# daughterboard_2sheetbackup.net
KiCad netlist of a schematic drawn in EAGLE
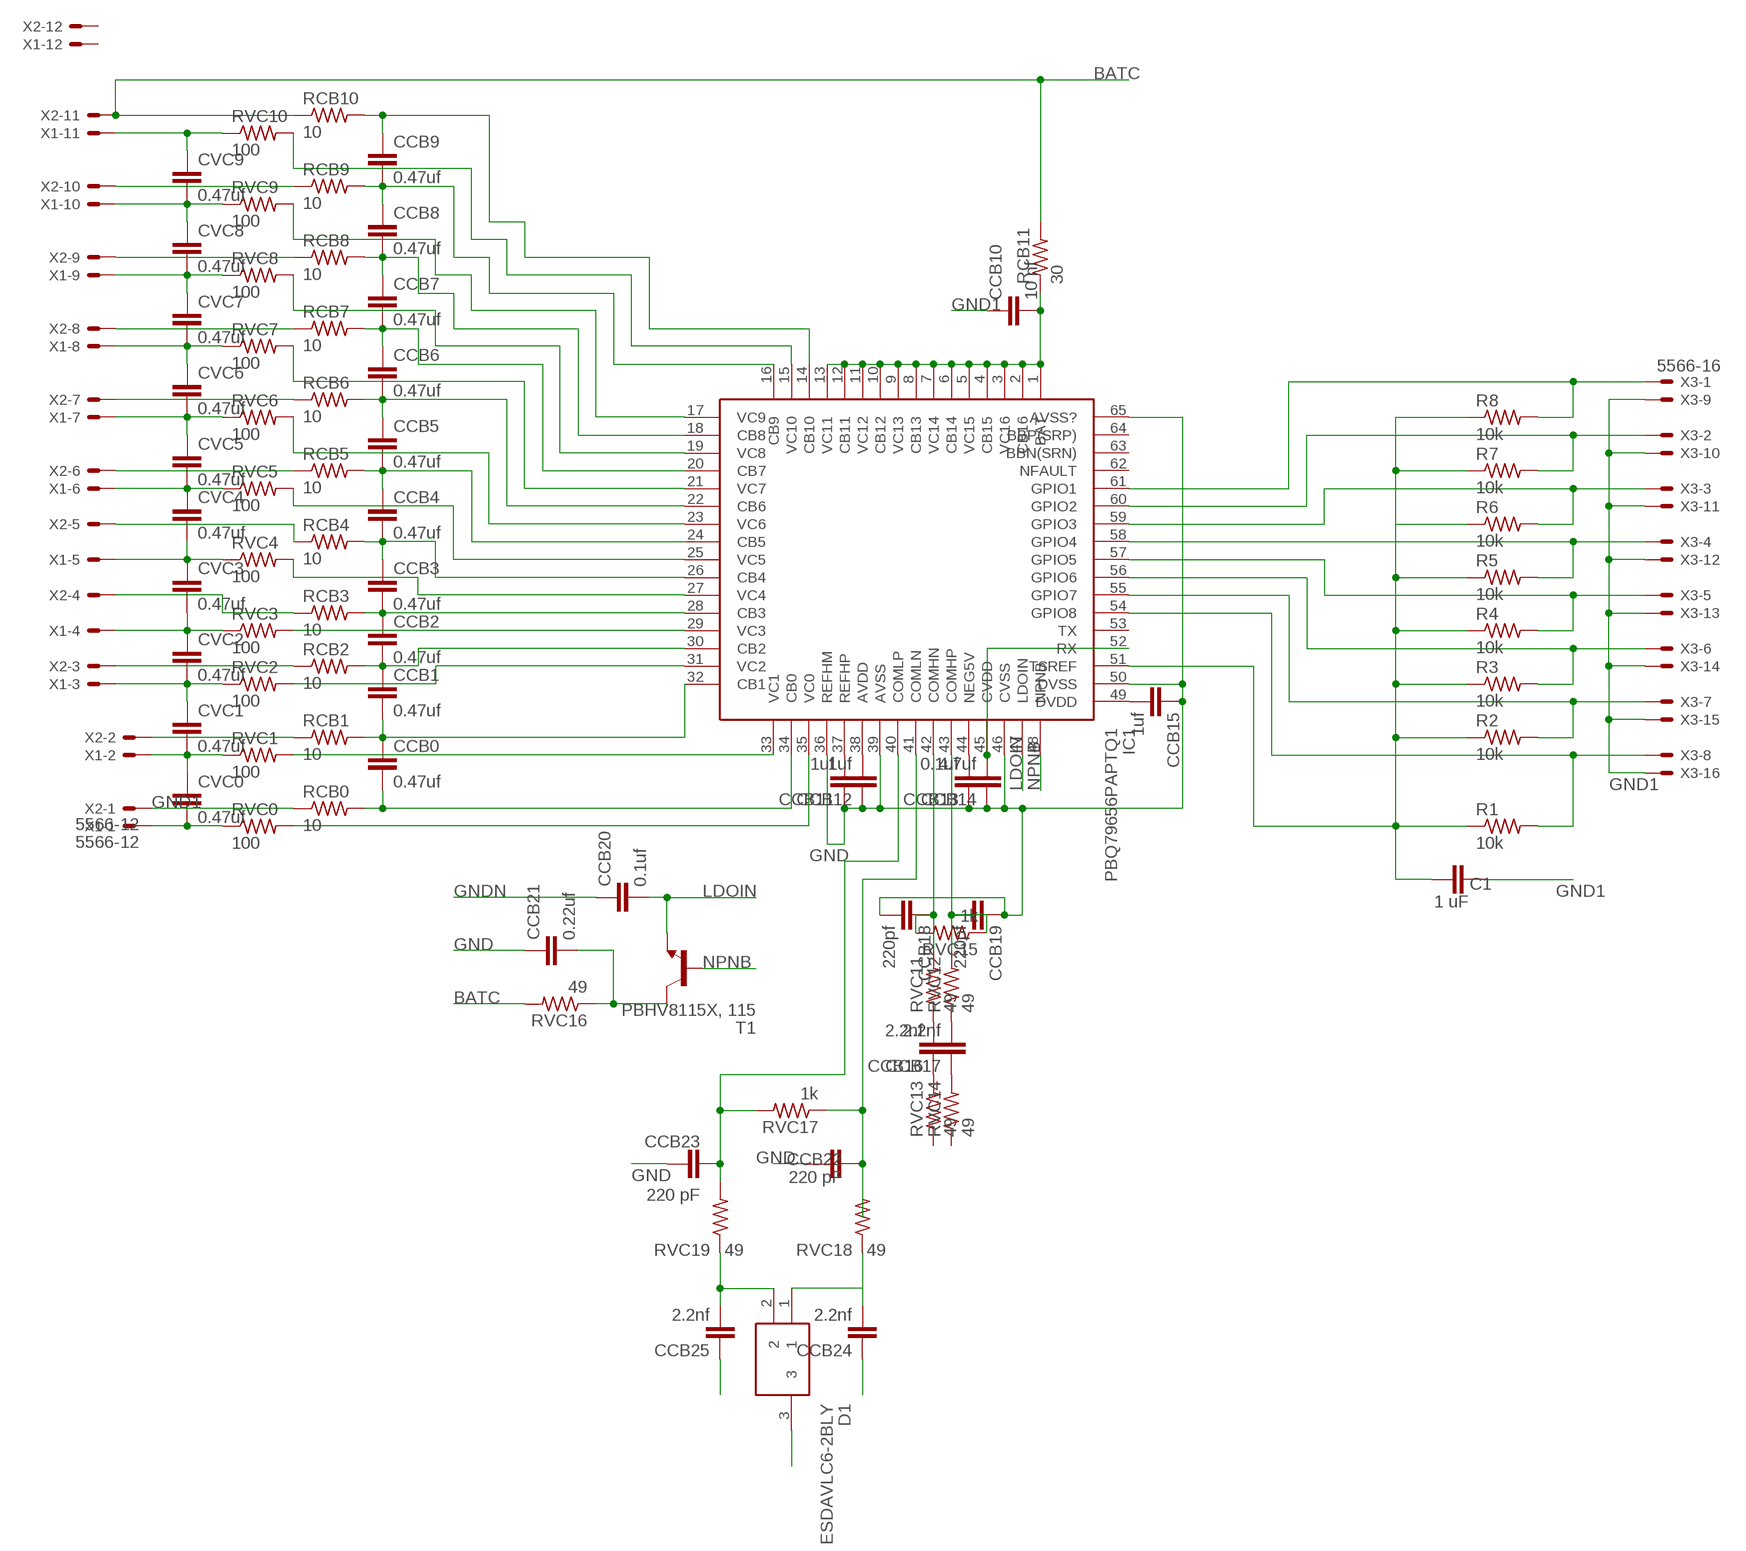
[diagram p0: schematic, sheet 1]
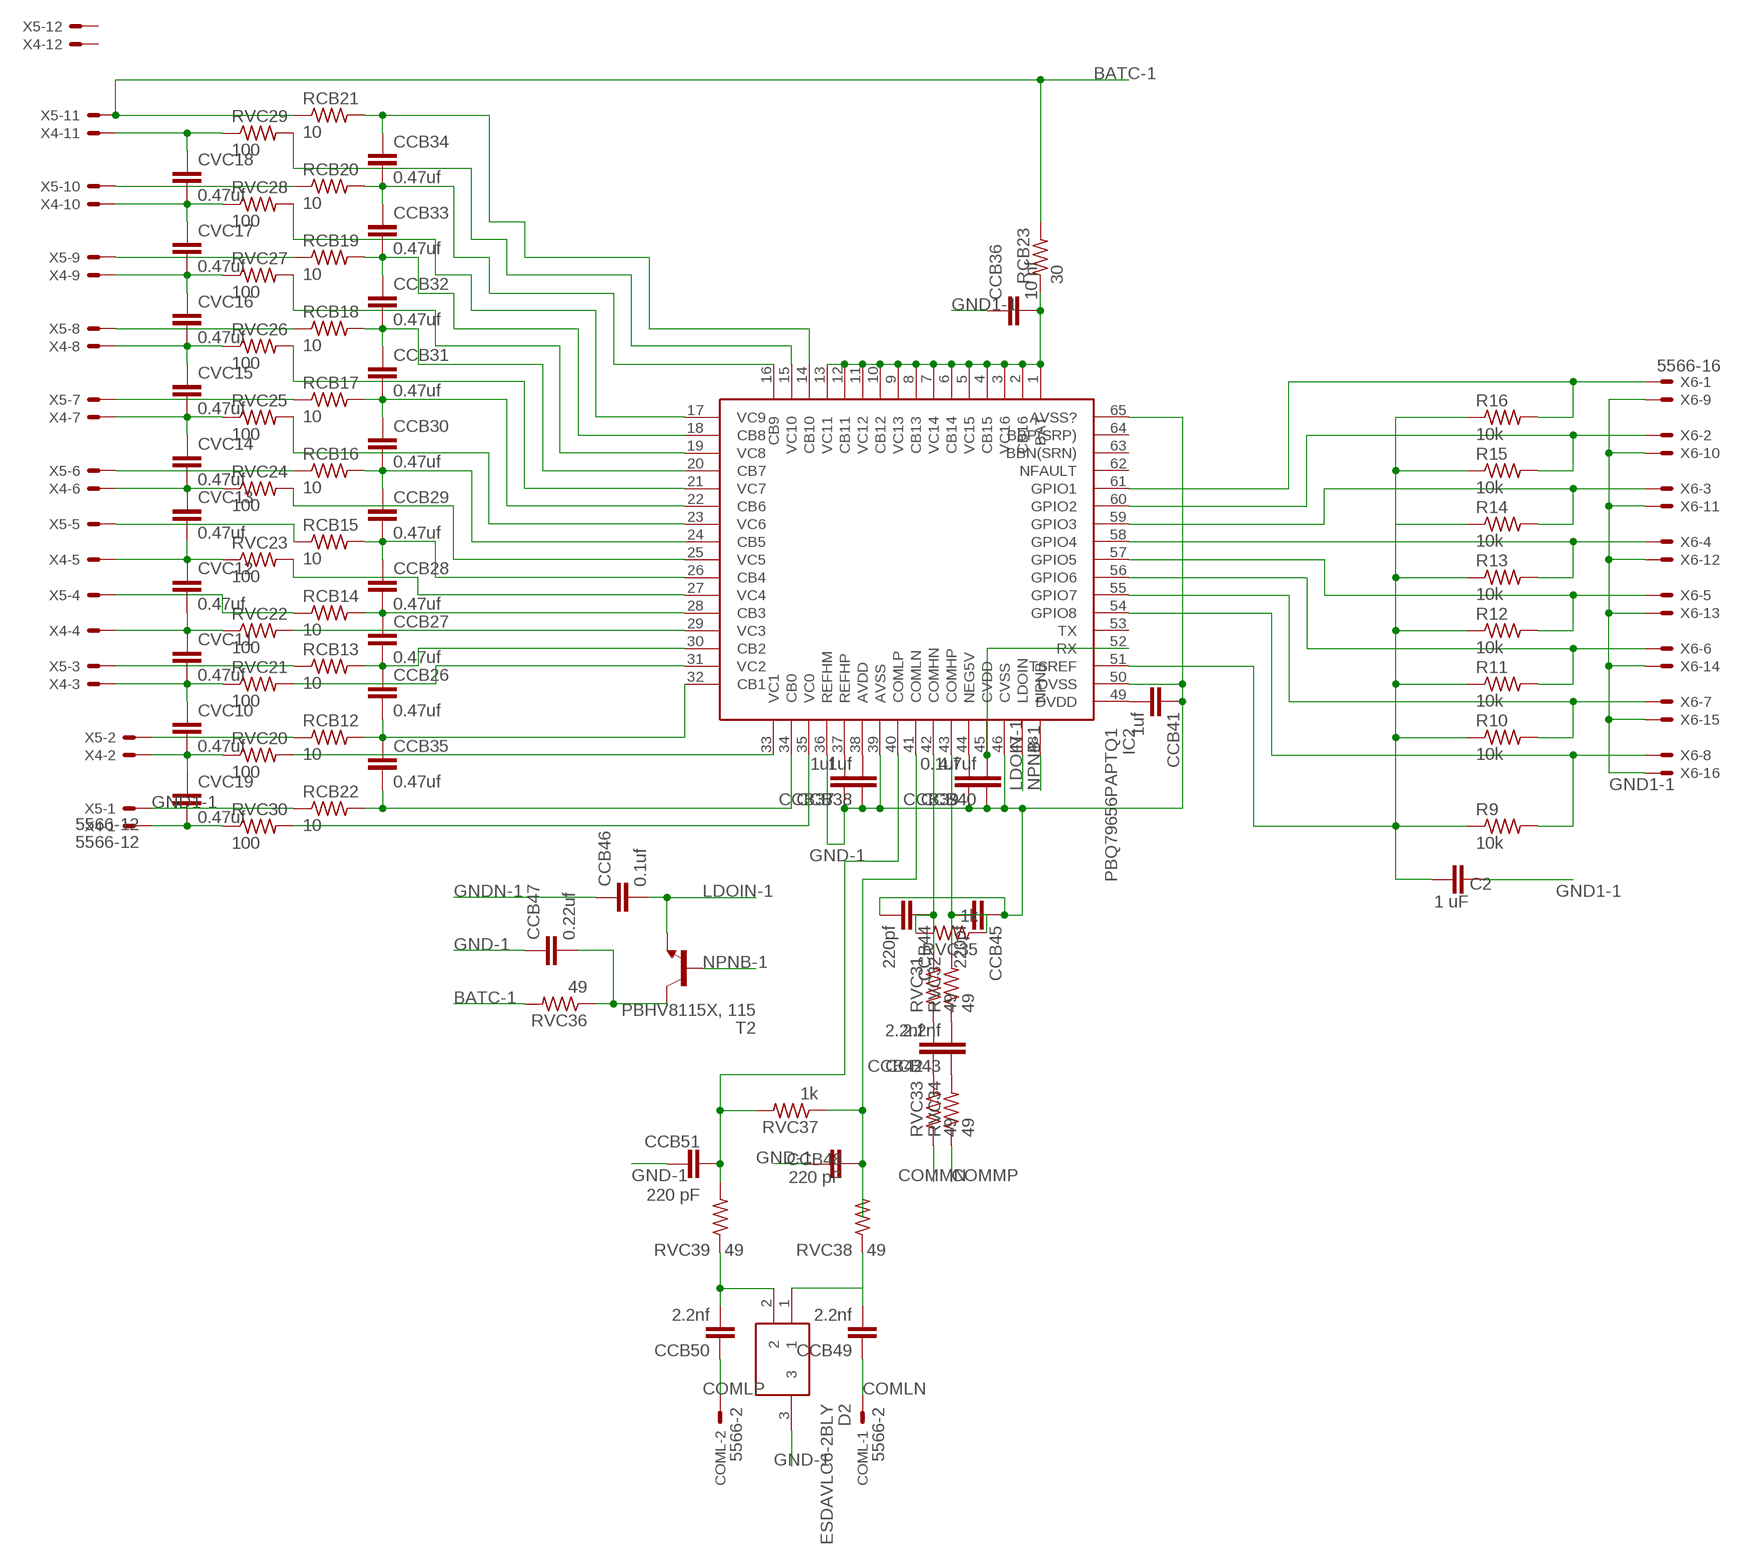
[diagram p1: schematic, sheet 2]

(export (version "E")
  (design (tool "Eeschema 10.0.6"))
  (components
    (comp (ref "C2")
      (value "1 uF")
      (footprint "eagle-import:C0603")
      (libsource (lib "eagle-import") (part "C-EUC0603"))
    )
    (comp (ref "CCB26")
      (value "0.47uf")
      (footprint "eagle-import:C0603")
      (libsource (lib "eagle-import") (part "C-EUC0603"))
    )
    (comp (ref "CCB27")
      (value "0.47uf")
      (footprint "eagle-import:C0603")
      (libsource (lib "eagle-import") (part "C-EUC0603"))
    )
    (comp (ref "CCB28")
      (value "0.47uf")
      (footprint "eagle-import:C0603")
      (libsource (lib "eagle-import") (part "C-EUC0603"))
    )
    (comp (ref "CCB29")
      (value "0.47uf")
      (footprint "eagle-import:C0603")
      (libsource (lib "eagle-import") (part "C-EUC0603"))
    )
    (comp (ref "CCB30")
      (value "0.47uf")
      (footprint "eagle-import:C0603")
      (libsource (lib "eagle-import") (part "C-EUC0603"))
    )
    (comp (ref "CCB31")
      (value "0.47uf")
      (footprint "eagle-import:C0603")
      (libsource (lib "eagle-import") (part "C-EUC0603"))
    )
    (comp (ref "CCB32")
      (value "0.47uf")
      (footprint "eagle-import:C0603")
      (libsource (lib "eagle-import") (part "C-EUC0603"))
    )
    (comp (ref "CCB33")
      (value "0.47uf")
      (footprint "eagle-import:C0603")
      (libsource (lib "eagle-import") (part "C-EUC0603"))
    )
    (comp (ref "CCB34")
      (value "0.47uf")
      (footprint "eagle-import:C0603")
      (libsource (lib "eagle-import") (part "C-EUC0603"))
    )
    (comp (ref "CCB35")
      (value "0.47uf")
      (footprint "eagle-import:C0603")
      (libsource (lib "eagle-import") (part "C-EUC0603"))
    )
    (comp (ref "CCB36")
      (value "10 nf")
      (footprint "eagle-import:C0603")
      (libsource (lib "eagle-import") (part "C-EUC0603"))
    )
    (comp (ref "CCB37")
      (value "1uf")
      (footprint "eagle-import:C0603")
      (libsource (lib "eagle-import") (part "C-EUC0603"))
    )
    (comp (ref "CCB38")
      (value "1uf")
      (footprint "eagle-import:C0603")
      (libsource (lib "eagle-import") (part "C-EUC0603"))
    )
    (comp (ref "CCB39")
      (value "0.1uf")
      (footprint "eagle-import:C0603")
      (libsource (lib "eagle-import") (part "C-EUC0603"))
    )
    (comp (ref "CCB40")
      (value "4.7uf")
      (footprint "eagle-import:C0603")
      (libsource (lib "eagle-import") (part "C-EUC0603"))
    )
    (comp (ref "CCB41")
      (value "1uf")
      (footprint "eagle-import:C0603")
      (libsource (lib "eagle-import") (part "C-EUC0603"))
    )
    (comp (ref "CCB42")
      (value "2.2nf")
      (footprint "eagle-import:C0603")
      (libsource (lib "eagle-import") (part "C-EUC0603"))
    )
    (comp (ref "CCB43")
      (value "2.2nf")
      (footprint "eagle-import:C0603")
      (libsource (lib "eagle-import") (part "C-EUC0603"))
    )
    (comp (ref "CCB44")
      (value "220pf")
      (footprint "eagle-import:C0603")
      (libsource (lib "eagle-import") (part "C-EUC0603"))
    )
    (comp (ref "CCB45")
      (value "220pf")
      (footprint "eagle-import:C0603")
      (libsource (lib "eagle-import") (part "C-EUC0603"))
    )
    (comp (ref "CCB46")
      (value "0.1uf")
      (footprint "eagle-import:C0603")
      (libsource (lib "eagle-import") (part "C-EUC0603"))
    )
    (comp (ref "CCB47")
      (value "0.22uf")
      (footprint "eagle-import:C0603")
      (libsource (lib "eagle-import") (part "C-EUC0603"))
    )
    (comp (ref "CCB48")
      (value "220 pF")
      (footprint "eagle-import:C0603")
      (libsource (lib "eagle-import") (part "C-EUC0603"))
    )
    (comp (ref "CCB49")
      (value "2.2nf")
      (footprint "eagle-import:C0603")
      (libsource (lib "eagle-import") (part "C-EUC0603"))
    )
    (comp (ref "CCB50")
      (value "2.2nf")
      (footprint "eagle-import:C0603")
      (libsource (lib "eagle-import") (part "C-EUC0603"))
    )
    (comp (ref "CCB51")
      (value "220 pF")
      (footprint "eagle-import:C0603")
      (libsource (lib "eagle-import") (part "C-EUC0603"))
    )
    (comp (ref "COML")
      (value "5566-2")
      (footprint "eagle-import:5566-2")
      (fields (field (name "MF") "MOLEX"))
      (libsource (lib "eagle-import") (part "5566-2"))
    )
    (comp (ref "CVC10")
      (value "0.47uf")
      (footprint "eagle-import:C0603")
      (libsource (lib "eagle-import") (part "C-EUC0603"))
    )
    (comp (ref "CVC11")
      (value "0.47uf")
      (footprint "eagle-import:C0603")
      (libsource (lib "eagle-import") (part "C-EUC0603"))
    )
    (comp (ref "CVC12")
      (value "0.47uf")
      (footprint "eagle-import:C0603")
      (libsource (lib "eagle-import") (part "C-EUC0603"))
    )
    (comp (ref "CVC13")
      (value "0.47uf")
      (footprint "eagle-import:C0603")
      (libsource (lib "eagle-import") (part "C-EUC0603"))
    )
    (comp (ref "CVC14")
      (value "0.47uf")
      (footprint "eagle-import:C0603")
      (libsource (lib "eagle-import") (part "C-EUC0603"))
    )
    (comp (ref "CVC15")
      (value "0.47uf")
      (footprint "eagle-import:C0603")
      (libsource (lib "eagle-import") (part "C-EUC0603"))
    )
    (comp (ref "CVC16")
      (value "0.47uf")
      (footprint "eagle-import:C0603")
      (libsource (lib "eagle-import") (part "C-EUC0603"))
    )
    (comp (ref "CVC17")
      (value "0.47uf")
      (footprint "eagle-import:C0603")
      (libsource (lib "eagle-import") (part "C-EUC0603"))
    )
    (comp (ref "CVC18")
      (value "0.47uf")
      (footprint "eagle-import:C0603")
      (libsource (lib "eagle-import") (part "C-EUC0603"))
    )
    (comp (ref "CVC19")
      (value "0.47uf")
      (footprint "eagle-import:C0603")
      (libsource (lib "eagle-import") (part "C-EUC0603"))
    )
    (comp (ref "D2")
      (value "ESDAVLC6-2BLY")
      (footprint "eagle-import:SOT95P255X150-3N")
      (fields (field (name "MOUSER_PART_NUMBER") "511-ESDAVLC6-2BLY"))
      (libsource (lib "eagle-import") (part "ESDAVLC6-2BLY"))
    )
    (comp (ref "IC2")
      (value "PBQ79656PAPTQ1")
      (footprint "eagle-import:QFP50P1200X1200X120-65N")
      (libsource (lib "eagle-import") (part "PBQ79656PAPTQ1"))
    )
    (comp (ref "R9")
      (value "10k")
      (footprint "eagle-import:R0603")
      (libsource (lib "eagle-import") (part "R-US_R0603"))
    )
    (comp (ref "R10")
      (value "10k")
      (footprint "eagle-import:R0603")
      (libsource (lib "eagle-import") (part "R-US_R0603"))
    )
    (comp (ref "R11")
      (value "10k")
      (footprint "eagle-import:R0603")
      (libsource (lib "eagle-import") (part "R-US_R0603"))
    )
    (comp (ref "R12")
      (value "10k")
      (footprint "eagle-import:R0603")
      (libsource (lib "eagle-import") (part "R-US_R0603"))
    )
    (comp (ref "R13")
      (value "10k")
      (footprint "eagle-import:R0603")
      (libsource (lib "eagle-import") (part "R-US_R0603"))
    )
    (comp (ref "R14")
      (value "10k")
      (footprint "eagle-import:R0603")
      (libsource (lib "eagle-import") (part "R-US_R0603"))
    )
    (comp (ref "R15")
      (value "10k")
      (footprint "eagle-import:R0603")
      (libsource (lib "eagle-import") (part "R-US_R0603"))
    )
    (comp (ref "R16")
      (value "10k")
      (footprint "eagle-import:R0603")
      (libsource (lib "eagle-import") (part "R-US_R0603"))
    )
    (comp (ref "RCB12")
      (value "10")
      (footprint "eagle-import:R0603")
      (libsource (lib "eagle-import") (part "R-US_R0603"))
    )
    (comp (ref "RCB13")
      (value "10")
      (footprint "eagle-import:R0603")
      (libsource (lib "eagle-import") (part "R-US_R0603"))
    )
    (comp (ref "RCB14")
      (value "10")
      (footprint "eagle-import:R0603")
      (libsource (lib "eagle-import") (part "R-US_R0603"))
    )
    (comp (ref "RCB15")
      (value "10")
      (footprint "eagle-import:R0603")
      (libsource (lib "eagle-import") (part "R-US_R0603"))
    )
    (comp (ref "RCB16")
      (value "10")
      (footprint "eagle-import:R0603")
      (libsource (lib "eagle-import") (part "R-US_R0603"))
    )
    (comp (ref "RCB17")
      (value "10")
      (footprint "eagle-import:R0603")
      (libsource (lib "eagle-import") (part "R-US_R0603"))
    )
    (comp (ref "RCB18")
      (value "10")
      (footprint "eagle-import:R0603")
      (libsource (lib "eagle-import") (part "R-US_R0603"))
    )
    (comp (ref "RCB19")
      (value "10")
      (footprint "eagle-import:R0603")
      (libsource (lib "eagle-import") (part "R-US_R0603"))
    )
    (comp (ref "RCB20")
      (value "10")
      (footprint "eagle-import:R0603")
      (libsource (lib "eagle-import") (part "R-US_R0603"))
    )
    (comp (ref "RCB21")
      (value "10")
      (footprint "eagle-import:R0603")
      (libsource (lib "eagle-import") (part "R-US_R0603"))
    )
    (comp (ref "RCB22")
      (value "10")
      (footprint "eagle-import:R0603")
      (libsource (lib "eagle-import") (part "R-US_R0603"))
    )
    (comp (ref "RCB23")
      (value "30")
      (footprint "eagle-import:R0603")
      (libsource (lib "eagle-import") (part "R-US_R0603"))
    )
    (comp (ref "RVC20")
      (value "100")
      (footprint "eagle-import:R0603")
      (libsource (lib "eagle-import") (part "R-US_R0603"))
    )
    (comp (ref "RVC21")
      (value "100")
      (footprint "eagle-import:R0603")
      (libsource (lib "eagle-import") (part "R-US_R0603"))
    )
    (comp (ref "RVC22")
      (value "100")
      (footprint "eagle-import:R0603")
      (libsource (lib "eagle-import") (part "R-US_R0603"))
    )
    (comp (ref "RVC23")
      (value "100")
      (footprint "eagle-import:R0603")
      (libsource (lib "eagle-import") (part "R-US_R0603"))
    )
    (comp (ref "RVC24")
      (value "100")
      (footprint "eagle-import:R0603")
      (libsource (lib "eagle-import") (part "R-US_R0603"))
    )
    (comp (ref "RVC25")
      (value "100")
      (footprint "eagle-import:R0603")
      (libsource (lib "eagle-import") (part "R-US_R0603"))
    )
    (comp (ref "RVC26")
      (value "100")
      (footprint "eagle-import:R0603")
      (libsource (lib "eagle-import") (part "R-US_R0603"))
    )
    (comp (ref "RVC27")
      (value "100")
      (footprint "eagle-import:R0603")
      (libsource (lib "eagle-import") (part "R-US_R0603"))
    )
    (comp (ref "RVC28")
      (value "100")
      (footprint "eagle-import:R0603")
      (libsource (lib "eagle-import") (part "R-US_R0603"))
    )
    (comp (ref "RVC29")
      (value "100")
      (footprint "eagle-import:R0603")
      (libsource (lib "eagle-import") (part "R-US_R0603"))
    )
    (comp (ref "RVC30")
      (value "100")
      (footprint "eagle-import:R0603")
      (libsource (lib "eagle-import") (part "R-US_R0603"))
    )
    (comp (ref "RVC31")
      (value "49")
      (footprint "eagle-import:R0603")
      (libsource (lib "eagle-import") (part "R-US_R0603"))
    )
    (comp (ref "RVC32")
      (value "49")
      (footprint "eagle-import:R0603")
      (libsource (lib "eagle-import") (part "R-US_R0603"))
    )
    (comp (ref "RVC33")
      (value "49")
      (footprint "eagle-import:R0603")
      (libsource (lib "eagle-import") (part "R-US_R0603"))
    )
    (comp (ref "RVC34")
      (value "49")
      (footprint "eagle-import:R0603")
      (libsource (lib "eagle-import") (part "R-US_R0603"))
    )
    (comp (ref "RVC35")
      (value "1k")
      (footprint "eagle-import:R0603")
      (libsource (lib "eagle-import") (part "R-US_R0603"))
    )
    (comp (ref "RVC36")
      (value "49")
      (footprint "eagle-import:R0603")
      (libsource (lib "eagle-import") (part "R-US_R0603"))
    )
    (comp (ref "RVC37")
      (value "1k")
      (footprint "eagle-import:R0603")
      (libsource (lib "eagle-import") (part "R-US_R0603"))
    )
    (comp (ref "RVC38")
      (value "49")
      (footprint "eagle-import:R0603")
      (libsource (lib "eagle-import") (part "R-US_R0603"))
    )
    (comp (ref "RVC39")
      (value "49")
      (footprint "eagle-import:R0603")
      (libsource (lib "eagle-import") (part "R-US_R0603"))
    )
    (comp (ref "T2")
      (value "PBHV8115X, 115")
      (footprint "eagle-import:SOT89-BCE")
      (libsource (lib "eagle-import") (part "-NPN-SOT89-BCEBC868"))
    )
    (comp (ref "X4")
      (value "5566-12")
      (footprint "eagle-import:5566-12")
      (fields (field (name "MF") "MOLEX"))
      (libsource (lib "eagle-import") (part "5566-12"))
    )
    (comp (ref "X5")
      (value "5566-12")
      (footprint "eagle-import:5566-12")
      (fields (field (name "MF") "MOLEX"))
      (libsource (lib "eagle-import") (part "5566-12"))
    )
    (comp (ref "X6")
      (value "5566-16")
      (footprint "eagle-import:5566-16")
      (fields (field (name "MF") "MOLEX"))
      (libsource (lib "eagle-import") (part "5566-16"))
    )
    (comp (ref "C1")
      (value "1 uF")
      (footprint "eagle-import:C2.5-2")
      (libsource (lib "eagle-import") (part "C2.5/2"))
    )
    (comp (ref "CCB0")
      (value "0.47uf")
      (footprint "eagle-import:C2.5-2")
      (libsource (lib "eagle-import") (part "C2.5/2"))
    )
    (comp (ref "CCB1")
      (value "0.47uf")
      (footprint "eagle-import:C2.5-2")
      (libsource (lib "eagle-import") (part "C2.5/2"))
    )
    (comp (ref "CCB2")
      (value "0.47uf")
      (footprint "eagle-import:C2.5-2")
      (libsource (lib "eagle-import") (part "C2.5/2"))
    )
    (comp (ref "CCB3")
      (value "0.47uf")
      (footprint "eagle-import:C2.5-2")
      (libsource (lib "eagle-import") (part "C2.5/2"))
    )
    (comp (ref "CCB4")
      (value "0.47uf")
      (footprint "eagle-import:C2.5-2")
      (libsource (lib "eagle-import") (part "C2.5/2"))
    )
    (comp (ref "CCB5")
      (value "0.47uf")
      (footprint "eagle-import:C2.5-2")
      (libsource (lib "eagle-import") (part "C2.5/2"))
    )
    (comp (ref "CCB6")
      (value "0.47uf")
      (footprint "eagle-import:C2.5-2")
      (libsource (lib "eagle-import") (part "C2.5/2"))
    )
    (comp (ref "CCB7")
      (value "0.47uf")
      (footprint "eagle-import:C2.5-2")
      (libsource (lib "eagle-import") (part "C2.5/2"))
    )
    (comp (ref "CCB8")
      (value "0.47uf")
      (footprint "eagle-import:C2.5-2")
      (libsource (lib "eagle-import") (part "C2.5/2"))
    )
    (comp (ref "CCB9")
      (value "0.47uf")
      (footprint "eagle-import:C2.5-2")
      (libsource (lib "eagle-import") (part "C2.5/2"))
    )
    (comp (ref "CCB10")
      (value "10 nf")
      (footprint "eagle-import:C2.5-2")
      (libsource (lib "eagle-import") (part "C2.5/2"))
    )
    (comp (ref "CCB11")
      (value "1uf")
      (footprint "eagle-import:C2.5-2")
      (libsource (lib "eagle-import") (part "C2.5/2"))
    )
    (comp (ref "CCB12")
      (value "1uf")
      (footprint "eagle-import:C2.5-2")
      (libsource (lib "eagle-import") (part "C2.5/2"))
    )
    (comp (ref "CCB13")
      (value "0.1uf")
      (footprint "eagle-import:C2.5-2")
      (libsource (lib "eagle-import") (part "C2.5/2"))
    )
    (comp (ref "CCB14")
      (value "4.7uf")
      (footprint "eagle-import:C2.5-2")
      (libsource (lib "eagle-import") (part "C2.5/2"))
    )
    (comp (ref "CCB15")
      (value "1uf")
      (footprint "eagle-import:C2.5-2")
      (libsource (lib "eagle-import") (part "C2.5/2"))
    )
    (comp (ref "CCB16")
      (value "2.2nf")
      (footprint "eagle-import:C2.5-2")
      (libsource (lib "eagle-import") (part "C2.5/2"))
    )
    (comp (ref "CCB17")
      (value "2.2nf")
      (footprint "eagle-import:C2.5-2")
      (libsource (lib "eagle-import") (part "C2.5/2"))
    )
    (comp (ref "CCB18")
      (value "220pf")
      (footprint "eagle-import:C2.5-2")
      (libsource (lib "eagle-import") (part "C2.5/2"))
    )
    (comp (ref "CCB19")
      (value "220pf")
      (footprint "eagle-import:C2.5-2")
      (libsource (lib "eagle-import") (part "C2.5/2"))
    )
    (comp (ref "CCB20")
      (value "0.1uf")
      (footprint "eagle-import:C2.5-2")
      (libsource (lib "eagle-import") (part "C2.5/2"))
    )
    (comp (ref "CCB21")
      (value "0.22uf")
      (footprint "eagle-import:C2.5-2")
      (libsource (lib "eagle-import") (part "C2.5/2"))
    )
    (comp (ref "CCB22")
      (value "220 pF")
      (footprint "eagle-import:C2.5-2")
      (libsource (lib "eagle-import") (part "C2.5/2"))
    )
    (comp (ref "CCB23")
      (value "220 pF")
      (footprint "eagle-import:C2.5-2")
      (libsource (lib "eagle-import") (part "C2.5/2"))
    )
    (comp (ref "CCB24")
      (value "2.2nf")
      (footprint "eagle-import:C2.5-2")
      (libsource (lib "eagle-import") (part "C2.5/2"))
    )
    (comp (ref "CCB25")
      (value "2.2nf")
      (footprint "eagle-import:C2.5-2")
      (libsource (lib "eagle-import") (part "C2.5/2"))
    )
    (comp (ref "CVC0")
      (value "0.47uf")
      (footprint "eagle-import:C2.5-2")
      (libsource (lib "eagle-import") (part "C2.5/2"))
    )
    (comp (ref "CVC1")
      (value "0.47uf")
      (footprint "eagle-import:C2.5-2")
      (libsource (lib "eagle-import") (part "C2.5/2"))
    )
    (comp (ref "CVC2")
      (value "0.47uf")
      (footprint "eagle-import:C2.5-2")
      (libsource (lib "eagle-import") (part "C2.5/2"))
    )
    (comp (ref "CVC3")
      (value "0.47uf")
      (footprint "eagle-import:C2.5-2")
      (libsource (lib "eagle-import") (part "C2.5/2"))
    )
    (comp (ref "CVC4")
      (value "0.47uf")
      (footprint "eagle-import:C2.5-2")
      (libsource (lib "eagle-import") (part "C2.5/2"))
    )
    (comp (ref "CVC5")
      (value "0.47uf")
      (footprint "eagle-import:C2.5-2")
      (libsource (lib "eagle-import") (part "C2.5/2"))
    )
    (comp (ref "CVC6")
      (value "0.47uf")
      (footprint "eagle-import:C2.5-2")
      (libsource (lib "eagle-import") (part "C2.5/2"))
    )
    (comp (ref "CVC7")
      (value "0.47uf")
      (footprint "eagle-import:C2.5-2")
      (libsource (lib "eagle-import") (part "C2.5/2"))
    )
    (comp (ref "CVC8")
      (value "0.47uf")
      (footprint "eagle-import:C2.5-2")
      (libsource (lib "eagle-import") (part "C2.5/2"))
    )
    (comp (ref "CVC9")
      (value "0.47uf")
      (footprint "eagle-import:C2.5-2")
      (libsource (lib "eagle-import") (part "C2.5/2"))
    )
    (comp (ref "D1")
      (value "ESDAVLC6-2BLY")
      (footprint "eagle-import:SOT95P255X150-3N")
      (fields (field (name "MOUSER_PART_NUMBER") "511-ESDAVLC6-2BLY"))
      (libsource (lib "eagle-import") (part "ESDAVLC6-2BLY"))
    )
    (comp (ref "IC1")
      (value "PBQ79656PAPTQ1")
      (footprint "eagle-import:QFP50P1200X1200X120-65N")
      (libsource (lib "eagle-import") (part "PBQ79656PAPTQ1"))
    )
    (comp (ref "R1")
      (value "10k")
      (footprint "eagle-import:R0603")
      (libsource (lib "eagle-import") (part "R-US_R0603"))
    )
    (comp (ref "R2")
      (value "10k")
      (footprint "eagle-import:R0603")
      (libsource (lib "eagle-import") (part "R-US_R0603"))
    )
    (comp (ref "R3")
      (value "10k")
      (footprint "eagle-import:R0603")
      (libsource (lib "eagle-import") (part "R-US_R0603"))
    )
    (comp (ref "R4")
      (value "10k")
      (footprint "eagle-import:R0603")
      (libsource (lib "eagle-import") (part "R-US_R0603"))
    )
    (comp (ref "R5")
      (value "10k")
      (footprint "eagle-import:R0603")
      (libsource (lib "eagle-import") (part "R-US_R0603"))
    )
    (comp (ref "R6")
      (value "10k")
      (footprint "eagle-import:R0603")
      (libsource (lib "eagle-import") (part "R-US_R0603"))
    )
    (comp (ref "R7")
      (value "10k")
      (footprint "eagle-import:R0603")
      (libsource (lib "eagle-import") (part "R-US_R0603"))
    )
    (comp (ref "R8")
      (value "10k")
      (footprint "eagle-import:R0603")
      (libsource (lib "eagle-import") (part "R-US_R0603"))
    )
    (comp (ref "RCB0")
      (value "10")
      (footprint "eagle-import:R0603")
      (libsource (lib "eagle-import") (part "R-US_R0603"))
    )
    (comp (ref "RCB1")
      (value "10")
      (footprint "eagle-import:R0603")
      (libsource (lib "eagle-import") (part "R-US_R0603"))
    )
    (comp (ref "RCB2")
      (value "10")
      (footprint "eagle-import:R0603")
      (libsource (lib "eagle-import") (part "R-US_R0603"))
    )
    (comp (ref "RCB3")
      (value "10")
      (footprint "eagle-import:R0603")
      (libsource (lib "eagle-import") (part "R-US_R0603"))
    )
    (comp (ref "RCB4")
      (value "10")
      (footprint "eagle-import:R0603")
      (libsource (lib "eagle-import") (part "R-US_R0603"))
    )
    (comp (ref "RCB5")
      (value "10")
      (footprint "eagle-import:R0603")
      (libsource (lib "eagle-import") (part "R-US_R0603"))
    )
    (comp (ref "RCB6")
      (value "10")
      (footprint "eagle-import:R0603")
      (libsource (lib "eagle-import") (part "R-US_R0603"))
    )
    (comp (ref "RCB7")
      (value "10")
      (footprint "eagle-import:R0603")
      (libsource (lib "eagle-import") (part "R-US_R0603"))
    )
    (comp (ref "RCB8")
      (value "10")
      (footprint "eagle-import:R0603")
      (libsource (lib "eagle-import") (part "R-US_R0603"))
    )
    (comp (ref "RCB9")
      (value "10")
      (footprint "eagle-import:R0603")
      (libsource (lib "eagle-import") (part "R-US_R0603"))
    )
    (comp (ref "RCB10")
      (value "10")
      (footprint "eagle-import:R0603")
      (libsource (lib "eagle-import") (part "R-US_R0603"))
    )
    (comp (ref "RCB11")
      (value "30")
      (footprint "eagle-import:R0603")
      (libsource (lib "eagle-import") (part "R-US_R0603"))
    )
    (comp (ref "RVC0")
      (value "100")
      (footprint "eagle-import:R0603")
      (libsource (lib "eagle-import") (part "R-US_R0603"))
    )
    (comp (ref "RVC1")
      (value "100")
      (footprint "eagle-import:R0603")
      (libsource (lib "eagle-import") (part "R-US_R0603"))
    )
    (comp (ref "RVC2")
      (value "100")
      (footprint "eagle-import:R0603")
      (libsource (lib "eagle-import") (part "R-US_R0603"))
    )
    (comp (ref "RVC3")
      (value "100")
      (footprint "eagle-import:R0603")
      (libsource (lib "eagle-import") (part "R-US_R0603"))
    )
    (comp (ref "RVC4")
      (value "100")
      (footprint "eagle-import:R0603")
      (libsource (lib "eagle-import") (part "R-US_R0603"))
    )
    (comp (ref "RVC5")
      (value "100")
      (footprint "eagle-import:R0603")
      (libsource (lib "eagle-import") (part "R-US_R0603"))
    )
    (comp (ref "RVC6")
      (value "100")
      (footprint "eagle-import:R0603")
      (libsource (lib "eagle-import") (part "R-US_R0603"))
    )
    (comp (ref "RVC7")
      (value "100")
      (footprint "eagle-import:R0603")
      (libsource (lib "eagle-import") (part "R-US_R0603"))
    )
    (comp (ref "RVC8")
      (value "100")
      (footprint "eagle-import:R0603")
      (libsource (lib "eagle-import") (part "R-US_R0603"))
    )
    (comp (ref "RVC9")
      (value "100")
      (footprint "eagle-import:R0603")
      (libsource (lib "eagle-import") (part "R-US_R0603"))
    )
    (comp (ref "RVC10")
      (value "100")
      (footprint "eagle-import:R0603")
      (libsource (lib "eagle-import") (part "R-US_R0603"))
    )
    (comp (ref "RVC11")
      (value "49")
      (footprint "eagle-import:R0603")
      (libsource (lib "eagle-import") (part "R-US_R0603"))
    )
    (comp (ref "RVC12")
      (value "49")
      (footprint "eagle-import:R0603")
      (libsource (lib "eagle-import") (part "R-US_R0603"))
    )
    (comp (ref "RVC13")
      (value "49")
      (footprint "eagle-import:R0603")
      (libsource (lib "eagle-import") (part "R-US_R0603"))
    )
    (comp (ref "RVC14")
      (value "49")
      (footprint "eagle-import:R0603")
      (libsource (lib "eagle-import") (part "R-US_R0603"))
    )
    (comp (ref "RVC15")
      (value "1k")
      (footprint "eagle-import:R0603")
      (libsource (lib "eagle-import") (part "R-US_R0603"))
    )
    (comp (ref "RVC16")
      (value "49")
      (footprint "eagle-import:R0603")
      (libsource (lib "eagle-import") (part "R-US_R0603"))
    )
    (comp (ref "RVC17")
      (value "1k")
      (footprint "eagle-import:R0603")
      (libsource (lib "eagle-import") (part "R-US_R0603"))
    )
    (comp (ref "RVC18")
      (value "49")
      (footprint "eagle-import:R0603")
      (libsource (lib "eagle-import") (part "R-US_R0603"))
    )
    (comp (ref "RVC19")
      (value "49")
      (footprint "eagle-import:R0603")
      (libsource (lib "eagle-import") (part "R-US_R0603"))
    )
    (comp (ref "T1")
      (value "PBHV8115X, 115")
      (footprint "eagle-import:SOT89-BCE")
      (libsource (lib "eagle-import") (part "-NPN-SOT89-BCEBC868"))
    )
    (comp (ref "X1")
      (value "5566-12")
      (footprint "eagle-import:5566-12")
      (fields (field (name "MF") "MOLEX"))
      (libsource (lib "eagle-import") (part "5566-12"))
    )
    (comp (ref "X2")
      (value "5566-12")
      (footprint "eagle-import:5566-12")
      (fields (field (name "MF") "MOLEX"))
      (libsource (lib "eagle-import") (part "5566-12"))
    )
    (comp (ref "X3")
      (value "5566-16")
      (footprint "eagle-import:5566-16")
      (fields (field (name "MF") "MOLEX"))
      (libsource (lib "eagle-import") (part "5566-16"))
    )
  )
  (nets
    (net (code "1") (name "BATC") (class "Default")
      (node (ref "RCB10") (pin "1") (pinfunction "1_1") (pintype "passive"))
      (node (ref "RCB11") (pin "2") (pinfunction "2_2") (pintype "passive"))
      (node (ref "RVC16") (pin "2") (pinfunction "2_2") (pintype "passive"))
      (node (ref "X2") (pin "11") (pinfunction "S_11") (pintype "passive"))
    )
    (net (code "2") (name "BATC-1") (class "Default")
      (node (ref "RCB21") (pin "1") (pinfunction "1_1") (pintype "passive"))
      (node (ref "RCB23") (pin "2") (pinfunction "2_2") (pintype "passive"))
      (node (ref "RVC36") (pin "2") (pinfunction "2_2") (pintype "passive"))
      (node (ref "X5") (pin "11") (pinfunction "S_11") (pintype "passive"))
    )
    (net (code "3") (name "COMLN") (class "Default")
      (node (ref "CCB49") (pin "1") (pinfunction "1_1") (pintype "passive"))
      (node (ref "COML") (pin "1") (pinfunction "S_1") (pintype "passive"))
    )
    (net (code "4") (name "COMLP") (class "Default")
      (node (ref "CCB50") (pin "1") (pinfunction "1_1") (pintype "passive"))
      (node (ref "COML") (pin "2") (pinfunction "S_2") (pintype "passive"))
    )
    (net (code "5") (name "COMMN") (class "Default")
      (node (ref "RVC33") (pin "1") (pinfunction "1_1") (pintype "passive"))
    )
    (net (code "6") (name "COMMP") (class "Default")
      (node (ref "RVC34") (pin "1") (pinfunction "1_1") (pintype "passive"))
    )
    (net (code "7") (name "GND") (class "Default")
      (node (ref "CCB11") (pin "1") (pinfunction "1_1") (pintype "passive"))
      (node (ref "CCB12") (pin "1") (pinfunction "1_1") (pintype "passive"))
      (node (ref "CCB13") (pin "1") (pinfunction "1_1") (pintype "passive"))
      (node (ref "CCB14") (pin "1") (pinfunction "1_1") (pintype "passive"))
      (node (ref "CCB15") (pin "1") (pinfunction "1_1") (pintype "passive"))
      (node (ref "CCB18") (pin "2") (pinfunction "2_2") (pintype "passive"))
      (node (ref "CCB19") (pin "1") (pinfunction "1_1") (pintype "passive"))
      (node (ref "CCB21") (pin "1") (pinfunction "1_1") (pintype "passive"))
      (node (ref "CCB22") (pin "1") (pinfunction "1_1") (pintype "passive"))
      (node (ref "CCB23") (pin "1") (pinfunction "1_1") (pintype "passive"))
      (node (ref "D1") (pin "3") (pinfunction "3_3") (pintype "bidirectional"))
      (node (ref "IC1") (pin "36") (pinfunction "REFHM_36") (pintype "bidirectional"))
      (node (ref "IC1") (pin "39") (pinfunction "AVSS_39") (pintype "bidirectional"))
      (node (ref "IC1") (pin "46") (pinfunction "CVSS_46") (pintype "bidirectional"))
      (node (ref "IC1") (pin "50") (pinfunction "DVSS_50") (pintype "bidirectional"))
      (node (ref "IC1") (pin "65") (pinfunction "AVSS?_65") (pintype "bidirectional"))
    )
    (net (code "8") (name "GND-1") (class "Default")
      (node (ref "CCB37") (pin "1") (pinfunction "1_1") (pintype "passive"))
      (node (ref "CCB38") (pin "1") (pinfunction "1_1") (pintype "passive"))
      (node (ref "CCB39") (pin "1") (pinfunction "1_1") (pintype "passive"))
      (node (ref "CCB40") (pin "1") (pinfunction "1_1") (pintype "passive"))
      (node (ref "CCB41") (pin "1") (pinfunction "1_1") (pintype "passive"))
      (node (ref "CCB44") (pin "2") (pinfunction "2_2") (pintype "passive"))
      (node (ref "CCB45") (pin "1") (pinfunction "1_1") (pintype "passive"))
      (node (ref "CCB47") (pin "1") (pinfunction "1_1") (pintype "passive"))
      (node (ref "CCB48") (pin "1") (pinfunction "1_1") (pintype "passive"))
      (node (ref "CCB51") (pin "1") (pinfunction "1_1") (pintype "passive"))
      (node (ref "D2") (pin "3") (pinfunction "3_3") (pintype "bidirectional"))
      (node (ref "IC2") (pin "36") (pinfunction "REFHM_36") (pintype "bidirectional"))
      (node (ref "IC2") (pin "39") (pinfunction "AVSS_39") (pintype "bidirectional"))
      (node (ref "IC2") (pin "46") (pinfunction "CVSS_46") (pintype "bidirectional"))
      (node (ref "IC2") (pin "50") (pinfunction "DVSS_50") (pintype "bidirectional"))
      (node (ref "IC2") (pin "65") (pinfunction "AVSS?_65") (pintype "bidirectional"))
    )
    (net (code "9") (name "GND1") (class "Default")
      (node (ref "C1") (pin "1") (pinfunction "1_1") (pintype "passive"))
      (node (ref "CCB10") (pin "1") (pinfunction "1_1") (pintype "passive"))
      (node (ref "RCB0") (pin "1") (pinfunction "1_1") (pintype "passive"))
      (node (ref "X2") (pin "1") (pinfunction "S_1") (pintype "passive"))
      (node (ref "X3") (pin "10") (pinfunction "S_10") (pintype "passive"))
      (node (ref "X3") (pin "11") (pinfunction "S_11") (pintype "passive"))
      (node (ref "X3") (pin "12") (pinfunction "S_12") (pintype "passive"))
      (node (ref "X3") (pin "13") (pinfunction "S_13") (pintype "passive"))
      (node (ref "X3") (pin "14") (pinfunction "S_14") (pintype "passive"))
      (node (ref "X3") (pin "15") (pinfunction "S_15") (pintype "passive"))
      (node (ref "X3") (pin "16") (pinfunction "S_16") (pintype "passive"))
      (node (ref "X3") (pin "9") (pinfunction "S_9") (pintype "passive"))
    )
    (net (code "10") (name "GND1-1") (class "Default")
      (node (ref "C2") (pin "1") (pinfunction "1_1") (pintype "passive"))
      (node (ref "CCB36") (pin "1") (pinfunction "1_1") (pintype "passive"))
      (node (ref "RCB22") (pin "1") (pinfunction "1_1") (pintype "passive"))
      (node (ref "X5") (pin "1") (pinfunction "S_1") (pintype "passive"))
      (node (ref "X6") (pin "10") (pinfunction "S_10") (pintype "passive"))
      (node (ref "X6") (pin "11") (pinfunction "S_11") (pintype "passive"))
      (node (ref "X6") (pin "12") (pinfunction "S_12") (pintype "passive"))
      (node (ref "X6") (pin "13") (pinfunction "S_13") (pintype "passive"))
      (node (ref "X6") (pin "14") (pinfunction "S_14") (pintype "passive"))
      (node (ref "X6") (pin "15") (pinfunction "S_15") (pintype "passive"))
      (node (ref "X6") (pin "16") (pinfunction "S_16") (pintype "passive"))
      (node (ref "X6") (pin "9") (pinfunction "S_9") (pintype "passive"))
    )
    (net (code "11") (name "GNDN") (class "Default")
      (node (ref "CCB20") (pin "1") (pinfunction "1_1") (pintype "passive"))
    )
    (net (code "12") (name "GNDN-1") (class "Default")
      (node (ref "CCB46") (pin "1") (pinfunction "1_1") (pintype "passive"))
    )
    (net (code "13") (name "LDOIN") (class "Default")
      (node (ref "CCB20") (pin "2") (pinfunction "2_2") (pintype "passive"))
      (node (ref "IC1") (pin "47") (pinfunction "LDOIN_47") (pintype "bidirectional"))
      (node (ref "T1") (pin "E") (pinfunction "E_E") (pintype "passive"))
    )
    (net (code "14") (name "LDOIN-1") (class "Default")
      (node (ref "CCB46") (pin "2") (pinfunction "2_2") (pintype "passive"))
      (node (ref "IC2") (pin "47") (pinfunction "LDOIN_47") (pintype "bidirectional"))
      (node (ref "T2") (pin "E") (pinfunction "E_E") (pintype "passive"))
    )
    (net (code "15") (name "NPNB") (class "Default")
      (node (ref "IC1") (pin "48") (pinfunction "NPNB_48") (pintype "bidirectional"))
      (node (ref "T1") (pin "B") (pinfunction "B_B") (pintype "passive"))
    )
    (net (code "16") (name "NPNB-1") (class "Default")
      (node (ref "IC2") (pin "48") (pinfunction "NPNB_48") (pintype "bidirectional"))
      (node (ref "T2") (pin "B") (pinfunction "B_B") (pintype "passive"))
    )
    (net (code "17") (name "Net-(CCB16-Pad1)") (class "Default")
      (node (ref "CCB16") (pin "1") (pinfunction "1_1") (pintype "passive"))
      (node (ref "RVC13") (pin "2") (pinfunction "2_2") (pintype "passive"))
    )
    (net (code "18") (name "Net-(CCB16-Pad2)") (class "Default")
      (node (ref "CCB16") (pin "2") (pinfunction "2_2") (pintype "passive"))
      (node (ref "RVC11") (pin "1") (pinfunction "1_1") (pintype "passive"))
    )
    (net (code "19") (name "Net-(CCB17-Pad1)") (class "Default")
      (node (ref "CCB17") (pin "1") (pinfunction "1_1") (pintype "passive"))
      (node (ref "RVC14") (pin "2") (pinfunction "2_2") (pintype "passive"))
    )
    (net (code "20") (name "Net-(CCB17-Pad2)") (class "Default")
      (node (ref "CCB17") (pin "2") (pinfunction "2_2") (pintype "passive"))
      (node (ref "RVC12") (pin "1") (pinfunction "1_1") (pintype "passive"))
    )
    (net (code "21") (name "Net-(CCB21-Pad2)") (class "Default")
      (node (ref "CCB21") (pin "2") (pinfunction "2_2") (pintype "passive"))
      (node (ref "RVC16") (pin "1") (pinfunction "1_1") (pintype "passive"))
      (node (ref "T1") (pin "C") (pinfunction "C_C") (pintype "passive"))
    )
    (net (code "22") (name "Net-(CCB24-Pad2)") (class "Default")
      (node (ref "CCB24") (pin "2") (pinfunction "2_2") (pintype "passive"))
      (node (ref "D1") (pin "1") (pinfunction "1_1") (pintype "bidirectional"))
      (node (ref "RVC18") (pin "1") (pinfunction "1_1") (pintype "passive"))
    )
    (net (code "23") (name "Net-(CCB25-Pad2)") (class "Default")
      (node (ref "CCB25") (pin "2") (pinfunction "2_2") (pintype "passive"))
      (node (ref "D1") (pin "2") (pinfunction "2_2") (pintype "bidirectional"))
      (node (ref "RVC19") (pin "1") (pinfunction "1_1") (pintype "passive"))
    )
    (net (code "24") (name "Net-(CCB42-Pad1)") (class "Default")
      (node (ref "CCB42") (pin "1") (pinfunction "1_1") (pintype "passive"))
      (node (ref "RVC33") (pin "2") (pinfunction "2_2") (pintype "passive"))
    )
    (net (code "25") (name "Net-(CCB42-Pad2)") (class "Default")
      (node (ref "CCB42") (pin "2") (pinfunction "2_2") (pintype "passive"))
      (node (ref "RVC31") (pin "1") (pinfunction "1_1") (pintype "passive"))
    )
    (net (code "26") (name "Net-(CCB43-Pad1)") (class "Default")
      (node (ref "CCB43") (pin "1") (pinfunction "1_1") (pintype "passive"))
      (node (ref "RVC34") (pin "2") (pinfunction "2_2") (pintype "passive"))
    )
    (net (code "27") (name "Net-(CCB43-Pad2)") (class "Default")
      (node (ref "CCB43") (pin "2") (pinfunction "2_2") (pintype "passive"))
      (node (ref "RVC32") (pin "1") (pinfunction "1_1") (pintype "passive"))
    )
    (net (code "28") (name "Net-(CCB47-Pad2)") (class "Default")
      (node (ref "CCB47") (pin "2") (pinfunction "2_2") (pintype "passive"))
      (node (ref "RVC36") (pin "1") (pinfunction "1_1") (pintype "passive"))
      (node (ref "T2") (pin "C") (pinfunction "C_C") (pintype "passive"))
    )
    (net (code "29") (name "Net-(CCB49-Pad2)") (class "Default")
      (node (ref "CCB49") (pin "2") (pinfunction "2_2") (pintype "passive"))
      (node (ref "D2") (pin "1") (pinfunction "1_1") (pintype "bidirectional"))
      (node (ref "RVC38") (pin "1") (pinfunction "1_1") (pintype "passive"))
    )
    (net (code "30") (name "Net-(CCB50-Pad2)") (class "Default")
      (node (ref "CCB50") (pin "2") (pinfunction "2_2") (pintype "passive"))
      (node (ref "D2") (pin "2") (pinfunction "2_2") (pintype "bidirectional"))
      (node (ref "RVC39") (pin "1") (pinfunction "1_1") (pintype "passive"))
    )
    (net (code "31") (name "Net-(IC1-AVDD)") (class "Default")
      (node (ref "CCB12") (pin "2") (pinfunction "2_2") (pintype "passive"))
      (node (ref "IC1") (pin "38") (pinfunction "AVDD_38") (pintype "bidirectional"))
    )
    (net (code "32") (name "Net-(IC1-BAT)") (class "Default")
      (node (ref "CCB10") (pin "2") (pinfunction "2_2") (pintype "passive"))
      (node (ref "IC1") (pin "1") (pinfunction "BAT_1") (pintype "bidirectional"))
      (node (ref "IC1") (pin "10") (pinfunction "CB12_10") (pintype "bidirectional"))
      (node (ref "IC1") (pin "11") (pinfunction "VC12_11") (pintype "bidirectional"))
      (node (ref "IC1") (pin "12") (pinfunction "CB11_12") (pintype "bidirectional"))
      (node (ref "IC1") (pin "13") (pinfunction "VC11_13") (pintype "bidirectional"))
      (node (ref "IC1") (pin "2") (pinfunction "CB16_2") (pintype "bidirectional"))
      (node (ref "IC1") (pin "3") (pinfunction "VC16_3") (pintype "bidirectional"))
      (node (ref "IC1") (pin "4") (pinfunction "CB15_4") (pintype "bidirectional"))
      (node (ref "IC1") (pin "5") (pinfunction "VC15_5") (pintype "bidirectional"))
      (node (ref "IC1") (pin "6") (pinfunction "CB14_6") (pintype "bidirectional"))
      (node (ref "IC1") (pin "7") (pinfunction "VC14_7") (pintype "bidirectional"))
      (node (ref "IC1") (pin "8") (pinfunction "CB13_8") (pintype "bidirectional"))
      (node (ref "IC1") (pin "9") (pinfunction "VC13_9") (pintype "bidirectional"))
      (node (ref "RCB11") (pin "1") (pinfunction "1_1") (pintype "passive"))
    )
    (net (code "33") (name "Net-(IC1-CB0)") (class "Default")
      (node (ref "CCB0") (pin "2") (pinfunction "2_2") (pintype "passive"))
      (node (ref "IC1") (pin "34") (pinfunction "CB0_34") (pintype "bidirectional"))
      (node (ref "RCB0") (pin "2") (pinfunction "2_2") (pintype "passive"))
    )
    (net (code "34") (name "Net-(IC1-CB1)") (class "Default")
      (node (ref "CCB0") (pin "1") (pinfunction "1_1") (pintype "passive"))
      (node (ref "CCB1") (pin "2") (pinfunction "2_2") (pintype "passive"))
      (node (ref "IC1") (pin "32") (pinfunction "CB1_32") (pintype "bidirectional"))
      (node (ref "RCB1") (pin "2") (pinfunction "2_2") (pintype "passive"))
    )
    (net (code "35") (name "Net-(IC1-CB2)") (class "Default")
      (node (ref "CCB1") (pin "1") (pinfunction "1_1") (pintype "passive"))
      (node (ref "CCB2") (pin "2") (pinfunction "2_2") (pintype "passive"))
      (node (ref "IC1") (pin "30") (pinfunction "CB2_30") (pintype "bidirectional"))
      (node (ref "RCB2") (pin "2") (pinfunction "2_2") (pintype "passive"))
    )
    (net (code "36") (name "Net-(IC1-CB3)") (class "Default")
      (node (ref "CCB2") (pin "1") (pinfunction "1_1") (pintype "passive"))
      (node (ref "CCB3") (pin "2") (pinfunction "2_2") (pintype "passive"))
      (node (ref "IC1") (pin "28") (pinfunction "CB3_28") (pintype "bidirectional"))
      (node (ref "RCB3") (pin "2") (pinfunction "2_2") (pintype "passive"))
    )
    (net (code "37") (name "Net-(IC1-CB4)") (class "Default")
      (node (ref "CCB3") (pin "1") (pinfunction "1_1") (pintype "passive"))
      (node (ref "CCB4") (pin "2") (pinfunction "2_2") (pintype "passive"))
      (node (ref "IC1") (pin "26") (pinfunction "CB4_26") (pintype "bidirectional"))
      (node (ref "RCB4") (pin "2") (pinfunction "2_2") (pintype "passive"))
    )
    (net (code "38") (name "Net-(IC1-CB5)") (class "Default")
      (node (ref "CCB4") (pin "1") (pinfunction "1_1") (pintype "passive"))
      (node (ref "CCB5") (pin "2") (pinfunction "2_2") (pintype "passive"))
      (node (ref "IC1") (pin "24") (pinfunction "CB5_24") (pintype "bidirectional"))
      (node (ref "RCB5") (pin "2") (pinfunction "2_2") (pintype "passive"))
    )
    (net (code "39") (name "Net-(IC1-CB6)") (class "Default")
      (node (ref "CCB5") (pin "1") (pinfunction "1_1") (pintype "passive"))
      (node (ref "CCB6") (pin "2") (pinfunction "2_2") (pintype "passive"))
      (node (ref "IC1") (pin "22") (pinfunction "CB6_22") (pintype "bidirectional"))
      (node (ref "RCB6") (pin "2") (pinfunction "2_2") (pintype "passive"))
    )
    (net (code "40") (name "Net-(IC1-CB7)") (class "Default")
      (node (ref "CCB6") (pin "1") (pinfunction "1_1") (pintype "passive"))
      (node (ref "CCB7") (pin "2") (pinfunction "2_2") (pintype "passive"))
      (node (ref "IC1") (pin "20") (pinfunction "CB7_20") (pintype "bidirectional"))
      (node (ref "RCB7") (pin "2") (pinfunction "2_2") (pintype "passive"))
    )
    (net (code "41") (name "Net-(IC1-CB8)") (class "Default")
      (node (ref "CCB7") (pin "1") (pinfunction "1_1") (pintype "passive"))
      (node (ref "CCB8") (pin "2") (pinfunction "2_2") (pintype "passive"))
      (node (ref "IC1") (pin "18") (pinfunction "CB8_18") (pintype "bidirectional"))
      (node (ref "RCB8") (pin "2") (pinfunction "2_2") (pintype "passive"))
    )
    (net (code "42") (name "Net-(IC1-CB9)") (class "Default")
      (node (ref "CCB8") (pin "1") (pinfunction "1_1") (pintype "passive"))
      (node (ref "CCB9") (pin "2") (pinfunction "2_2") (pintype "passive"))
      (node (ref "IC1") (pin "16") (pinfunction "CB9_16") (pintype "bidirectional"))
      (node (ref "RCB9") (pin "2") (pinfunction "2_2") (pintype "passive"))
    )
    (net (code "43") (name "Net-(IC1-CB10)") (class "Default")
      (node (ref "CCB9") (pin "1") (pinfunction "1_1") (pintype "passive"))
      (node (ref "IC1") (pin "14") (pinfunction "CB10_14") (pintype "bidirectional"))
      (node (ref "RCB10") (pin "2") (pinfunction "2_2") (pintype "passive"))
    )
    (net (code "44") (name "Net-(IC1-COMHN)") (class "Default")
      (node (ref "CCB18") (pin "1") (pinfunction "1_1") (pintype "passive"))
      (node (ref "IC1") (pin "42") (pinfunction "COMHN_42") (pintype "bidirectional"))
      (node (ref "RVC11") (pin "2") (pinfunction "2_2") (pintype "passive"))
      (node (ref "RVC15") (pin "2") (pinfunction "2_2") (pintype "passive"))
    )
    (net (code "45") (name "Net-(IC1-COMHP)") (class "Default")
      (node (ref "CCB19") (pin "2") (pinfunction "2_2") (pintype "passive"))
      (node (ref "IC1") (pin "43") (pinfunction "COMHP_43") (pintype "bidirectional"))
      (node (ref "RVC12") (pin "2") (pinfunction "2_2") (pintype "passive"))
      (node (ref "RVC15") (pin "1") (pinfunction "1_1") (pintype "passive"))
    )
    (net (code "46") (name "Net-(IC1-COMLN)") (class "Default")
      (node (ref "CCB22") (pin "2") (pinfunction "2_2") (pintype "passive"))
      (node (ref "IC1") (pin "41") (pinfunction "COMLN_41") (pintype "bidirectional"))
      (node (ref "RVC17") (pin "1") (pinfunction "1_1") (pintype "passive"))
      (node (ref "RVC18") (pin "2") (pinfunction "2_2") (pintype "passive"))
    )
    (net (code "47") (name "Net-(IC1-COMLP)") (class "Default")
      (node (ref "CCB23") (pin "2") (pinfunction "2_2") (pintype "passive"))
      (node (ref "IC1") (pin "40") (pinfunction "COMLP_40") (pintype "bidirectional"))
      (node (ref "RVC17") (pin "2") (pinfunction "2_2") (pintype "passive"))
      (node (ref "RVC19") (pin "2") (pinfunction "2_2") (pintype "passive"))
    )
    (net (code "48") (name "Net-(IC1-CVDD)") (class "Default")
      (node (ref "CCB14") (pin "2") (pinfunction "2_2") (pintype "passive"))
      (node (ref "IC1") (pin "45") (pinfunction "CVDD_45") (pintype "bidirectional"))
      (node (ref "IC1") (pin "52") (pinfunction "RX_52") (pintype "bidirectional"))
    )
    (net (code "49") (name "Net-(IC1-DVDD)") (class "Default")
      (node (ref "CCB15") (pin "2") (pinfunction "2_2") (pintype "passive"))
      (node (ref "IC1") (pin "49") (pinfunction "DVDD_49") (pintype "bidirectional"))
    )
    (net (code "50") (name "Net-(IC1-GPIO1)") (class "Default")
      (node (ref "IC1") (pin "61") (pinfunction "GPIO1_61") (pintype "bidirectional"))
      (node (ref "R8") (pin "2") (pinfunction "2_2") (pintype "passive"))
      (node (ref "X3") (pin "1") (pinfunction "S_1") (pintype "passive"))
    )
    (net (code "51") (name "Net-(IC1-GPIO2)") (class "Default")
      (node (ref "IC1") (pin "60") (pinfunction "GPIO2_60") (pintype "bidirectional"))
      (node (ref "R7") (pin "2") (pinfunction "2_2") (pintype "passive"))
      (node (ref "X3") (pin "2") (pinfunction "S_2") (pintype "passive"))
    )
    (net (code "52") (name "Net-(IC1-GPIO3)") (class "Default")
      (node (ref "IC1") (pin "59") (pinfunction "GPIO3_59") (pintype "bidirectional"))
      (node (ref "R6") (pin "2") (pinfunction "2_2") (pintype "passive"))
      (node (ref "X3") (pin "3") (pinfunction "S_3") (pintype "passive"))
    )
    (net (code "53") (name "Net-(IC1-GPIO4)") (class "Default")
      (node (ref "IC1") (pin "58") (pinfunction "GPIO4_58") (pintype "bidirectional"))
      (node (ref "R5") (pin "2") (pinfunction "2_2") (pintype "passive"))
      (node (ref "X3") (pin "4") (pinfunction "S_4") (pintype "passive"))
    )
    (net (code "54") (name "Net-(IC1-GPIO5)") (class "Default")
      (node (ref "IC1") (pin "57") (pinfunction "GPIO5_57") (pintype "bidirectional"))
      (node (ref "R4") (pin "2") (pinfunction "2_2") (pintype "passive"))
      (node (ref "X3") (pin "5") (pinfunction "S_5") (pintype "passive"))
    )
    (net (code "55") (name "Net-(IC1-GPIO6)") (class "Default")
      (node (ref "IC1") (pin "56") (pinfunction "GPIO6_56") (pintype "bidirectional"))
      (node (ref "R3") (pin "2") (pinfunction "2_2") (pintype "passive"))
      (node (ref "X3") (pin "6") (pinfunction "S_6") (pintype "passive"))
    )
    (net (code "56") (name "Net-(IC1-GPIO7)") (class "Default")
      (node (ref "IC1") (pin "55") (pinfunction "GPIO7_55") (pintype "bidirectional"))
      (node (ref "R2") (pin "2") (pinfunction "2_2") (pintype "passive"))
      (node (ref "X3") (pin "7") (pinfunction "S_7") (pintype "passive"))
    )
    (net (code "57") (name "Net-(IC1-GPIO8)") (class "Default")
      (node (ref "IC1") (pin "54") (pinfunction "GPIO8_54") (pintype "bidirectional"))
      (node (ref "R1") (pin "2") (pinfunction "2_2") (pintype "passive"))
      (node (ref "X3") (pin "8") (pinfunction "S_8") (pintype "passive"))
    )
    (net (code "58") (name "Net-(IC1-NEG5V)") (class "Default")
      (node (ref "CCB13") (pin "2") (pinfunction "2_2") (pintype "passive"))
      (node (ref "IC1") (pin "44") (pinfunction "NEG5V_44") (pintype "bidirectional"))
    )
    (net (code "59") (name "Net-(IC1-REFHP)") (class "Default")
      (node (ref "CCB11") (pin "2") (pinfunction "2_2") (pintype "passive"))
      (node (ref "IC1") (pin "37") (pinfunction "REFHP_37") (pintype "bidirectional"))
    )
    (net (code "60") (name "Net-(IC1-TSREF)") (class "Default")
      (node (ref "C1") (pin "2") (pinfunction "2_2") (pintype "passive"))
      (node (ref "IC1") (pin "51") (pinfunction "TSREF_51") (pintype "bidirectional"))
      (node (ref "R1") (pin "1") (pinfunction "1_1") (pintype "passive"))
      (node (ref "R2") (pin "1") (pinfunction "1_1") (pintype "passive"))
      (node (ref "R3") (pin "1") (pinfunction "1_1") (pintype "passive"))
      (node (ref "R4") (pin "1") (pinfunction "1_1") (pintype "passive"))
      (node (ref "R5") (pin "1") (pinfunction "1_1") (pintype "passive"))
      (node (ref "R6") (pin "1") (pinfunction "1_1") (pintype "passive"))
      (node (ref "R7") (pin "1") (pinfunction "1_1") (pintype "passive"))
      (node (ref "R8") (pin "1") (pinfunction "1_1") (pintype "passive"))
    )
    (net (code "61") (name "Net-(IC1-VC0)") (class "Default")
      (node (ref "IC1") (pin "35") (pinfunction "VC0_35") (pintype "bidirectional"))
      (node (ref "RVC0") (pin "2") (pinfunction "2_2") (pintype "passive"))
    )
    (net (code "62") (name "Net-(IC1-VC1)") (class "Default")
      (node (ref "IC1") (pin "33") (pinfunction "VC1_33") (pintype "bidirectional"))
      (node (ref "RVC1") (pin "2") (pinfunction "2_2") (pintype "passive"))
    )
    (net (code "63") (name "Net-(IC1-VC2)") (class "Default")
      (node (ref "IC1") (pin "31") (pinfunction "VC2_31") (pintype "bidirectional"))
      (node (ref "RVC2") (pin "2") (pinfunction "2_2") (pintype "passive"))
    )
    (net (code "64") (name "Net-(IC1-VC3)") (class "Default")
      (node (ref "IC1") (pin "29") (pinfunction "VC3_29") (pintype "bidirectional"))
      (node (ref "RVC3") (pin "2") (pinfunction "2_2") (pintype "passive"))
    )
    (net (code "65") (name "Net-(IC1-VC4)") (class "Default")
      (node (ref "IC1") (pin "27") (pinfunction "VC4_27") (pintype "bidirectional"))
      (node (ref "RVC4") (pin "2") (pinfunction "2_2") (pintype "passive"))
    )
    (net (code "66") (name "Net-(IC1-VC5)") (class "Default")
      (node (ref "IC1") (pin "25") (pinfunction "VC5_25") (pintype "bidirectional"))
      (node (ref "RVC5") (pin "2") (pinfunction "2_2") (pintype "passive"))
    )
    (net (code "67") (name "Net-(IC1-VC6)") (class "Default")
      (node (ref "IC1") (pin "23") (pinfunction "VC6_23") (pintype "bidirectional"))
      (node (ref "RVC6") (pin "2") (pinfunction "2_2") (pintype "passive"))
    )
    (net (code "68") (name "Net-(IC1-VC7)") (class "Default")
      (node (ref "IC1") (pin "21") (pinfunction "VC7_21") (pintype "bidirectional"))
      (node (ref "RVC7") (pin "2") (pinfunction "2_2") (pintype "passive"))
    )
    (net (code "69") (name "Net-(IC1-VC8)") (class "Default")
      (node (ref "IC1") (pin "19") (pinfunction "VC8_19") (pintype "bidirectional"))
      (node (ref "RVC8") (pin "2") (pinfunction "2_2") (pintype "passive"))
    )
    (net (code "70") (name "Net-(IC1-VC9)") (class "Default")
      (node (ref "IC1") (pin "17") (pinfunction "VC9_17") (pintype "bidirectional"))
      (node (ref "RVC9") (pin "2") (pinfunction "2_2") (pintype "passive"))
    )
    (net (code "71") (name "Net-(IC1-VC10)") (class "Default")
      (node (ref "IC1") (pin "15") (pinfunction "VC10_15") (pintype "bidirectional"))
      (node (ref "RVC10") (pin "2") (pinfunction "2_2") (pintype "passive"))
    )
    (net (code "72") (name "Net-(IC2-AVDD)") (class "Default")
      (node (ref "CCB38") (pin "2") (pinfunction "2_2") (pintype "passive"))
      (node (ref "IC2") (pin "38") (pinfunction "AVDD_38") (pintype "bidirectional"))
    )
    (net (code "73") (name "Net-(IC2-BAT)") (class "Default")
      (node (ref "CCB36") (pin "2") (pinfunction "2_2") (pintype "passive"))
      (node (ref "IC2") (pin "1") (pinfunction "BAT_1") (pintype "bidirectional"))
      (node (ref "IC2") (pin "10") (pinfunction "CB12_10") (pintype "bidirectional"))
      (node (ref "IC2") (pin "11") (pinfunction "VC12_11") (pintype "bidirectional"))
      (node (ref "IC2") (pin "12") (pinfunction "CB11_12") (pintype "bidirectional"))
      (node (ref "IC2") (pin "13") (pinfunction "VC11_13") (pintype "bidirectional"))
      (node (ref "IC2") (pin "2") (pinfunction "CB16_2") (pintype "bidirectional"))
      (node (ref "IC2") (pin "3") (pinfunction "VC16_3") (pintype "bidirectional"))
      (node (ref "IC2") (pin "4") (pinfunction "CB15_4") (pintype "bidirectional"))
      (node (ref "IC2") (pin "5") (pinfunction "VC15_5") (pintype "bidirectional"))
      (node (ref "IC2") (pin "6") (pinfunction "CB14_6") (pintype "bidirectional"))
      (node (ref "IC2") (pin "7") (pinfunction "VC14_7") (pintype "bidirectional"))
      (node (ref "IC2") (pin "8") (pinfunction "CB13_8") (pintype "bidirectional"))
      (node (ref "IC2") (pin "9") (pinfunction "VC13_9") (pintype "bidirectional"))
      (node (ref "RCB23") (pin "1") (pinfunction "1_1") (pintype "passive"))
    )
    (net (code "74") (name "Net-(IC2-CB0)") (class "Default")
      (node (ref "CCB35") (pin "2") (pinfunction "2_2") (pintype "passive"))
      (node (ref "IC2") (pin "34") (pinfunction "CB0_34") (pintype "bidirectional"))
      (node (ref "RCB22") (pin "2") (pinfunction "2_2") (pintype "passive"))
    )
    (net (code "75") (name "Net-(IC2-CB1)") (class "Default")
      (node (ref "CCB26") (pin "2") (pinfunction "2_2") (pintype "passive"))
      (node (ref "CCB35") (pin "1") (pinfunction "1_1") (pintype "passive"))
      (node (ref "IC2") (pin "32") (pinfunction "CB1_32") (pintype "bidirectional"))
      (node (ref "RCB12") (pin "2") (pinfunction "2_2") (pintype "passive"))
    )
    (net (code "76") (name "Net-(IC2-CB2)") (class "Default")
      (node (ref "CCB26") (pin "1") (pinfunction "1_1") (pintype "passive"))
      (node (ref "CCB27") (pin "2") (pinfunction "2_2") (pintype "passive"))
      (node (ref "IC2") (pin "30") (pinfunction "CB2_30") (pintype "bidirectional"))
      (node (ref "RCB13") (pin "2") (pinfunction "2_2") (pintype "passive"))
    )
    (net (code "77") (name "Net-(IC2-CB3)") (class "Default")
      (node (ref "CCB27") (pin "1") (pinfunction "1_1") (pintype "passive"))
      (node (ref "CCB28") (pin "2") (pinfunction "2_2") (pintype "passive"))
      (node (ref "IC2") (pin "28") (pinfunction "CB3_28") (pintype "bidirectional"))
      (node (ref "RCB14") (pin "2") (pinfunction "2_2") (pintype "passive"))
    )
    (net (code "78") (name "Net-(IC2-CB4)") (class "Default")
      (node (ref "CCB28") (pin "1") (pinfunction "1_1") (pintype "passive"))
      (node (ref "CCB29") (pin "2") (pinfunction "2_2") (pintype "passive"))
      (node (ref "IC2") (pin "26") (pinfunction "CB4_26") (pintype "bidirectional"))
      (node (ref "RCB15") (pin "2") (pinfunction "2_2") (pintype "passive"))
    )
    (net (code "79") (name "Net-(IC2-CB5)") (class "Default")
      (node (ref "CCB29") (pin "1") (pinfunction "1_1") (pintype "passive"))
      (node (ref "CCB30") (pin "2") (pinfunction "2_2") (pintype "passive"))
      (node (ref "IC2") (pin "24") (pinfunction "CB5_24") (pintype "bidirectional"))
      (node (ref "RCB16") (pin "2") (pinfunction "2_2") (pintype "passive"))
    )
    (net (code "80") (name "Net-(IC2-CB6)") (class "Default")
      (node (ref "CCB30") (pin "1") (pinfunction "1_1") (pintype "passive"))
      (node (ref "CCB31") (pin "2") (pinfunction "2_2") (pintype "passive"))
      (node (ref "IC2") (pin "22") (pinfunction "CB6_22") (pintype "bidirectional"))
      (node (ref "RCB17") (pin "2") (pinfunction "2_2") (pintype "passive"))
    )
    (net (code "81") (name "Net-(IC2-CB7)") (class "Default")
      (node (ref "CCB31") (pin "1") (pinfunction "1_1") (pintype "passive"))
      (node (ref "CCB32") (pin "2") (pinfunction "2_2") (pintype "passive"))
      (node (ref "IC2") (pin "20") (pinfunction "CB7_20") (pintype "bidirectional"))
      (node (ref "RCB18") (pin "2") (pinfunction "2_2") (pintype "passive"))
    )
    (net (code "82") (name "Net-(IC2-CB8)") (class "Default")
      (node (ref "CCB32") (pin "1") (pinfunction "1_1") (pintype "passive"))
      (node (ref "CCB33") (pin "2") (pinfunction "2_2") (pintype "passive"))
      (node (ref "IC2") (pin "18") (pinfunction "CB8_18") (pintype "bidirectional"))
      (node (ref "RCB19") (pin "2") (pinfunction "2_2") (pintype "passive"))
    )
    (net (code "83") (name "Net-(IC2-CB9)") (class "Default")
      (node (ref "CCB33") (pin "1") (pinfunction "1_1") (pintype "passive"))
      (node (ref "CCB34") (pin "2") (pinfunction "2_2") (pintype "passive"))
      (node (ref "IC2") (pin "16") (pinfunction "CB9_16") (pintype "bidirectional"))
      (node (ref "RCB20") (pin "2") (pinfunction "2_2") (pintype "passive"))
    )
    (net (code "84") (name "Net-(IC2-CB10)") (class "Default")
      (node (ref "CCB34") (pin "1") (pinfunction "1_1") (pintype "passive"))
      (node (ref "IC2") (pin "14") (pinfunction "CB10_14") (pintype "bidirectional"))
      (node (ref "RCB21") (pin "2") (pinfunction "2_2") (pintype "passive"))
    )
    (net (code "85") (name "Net-(IC2-COMHN)") (class "Default")
      (node (ref "CCB44") (pin "1") (pinfunction "1_1") (pintype "passive"))
      (node (ref "IC2") (pin "42") (pinfunction "COMHN_42") (pintype "bidirectional"))
      (node (ref "RVC31") (pin "2") (pinfunction "2_2") (pintype "passive"))
      (node (ref "RVC35") (pin "2") (pinfunction "2_2") (pintype "passive"))
    )
    (net (code "86") (name "Net-(IC2-COMHP)") (class "Default")
      (node (ref "CCB45") (pin "2") (pinfunction "2_2") (pintype "passive"))
      (node (ref "IC2") (pin "43") (pinfunction "COMHP_43") (pintype "bidirectional"))
      (node (ref "RVC32") (pin "2") (pinfunction "2_2") (pintype "passive"))
      (node (ref "RVC35") (pin "1") (pinfunction "1_1") (pintype "passive"))
    )
    (net (code "87") (name "Net-(IC2-COMLN)") (class "Default")
      (node (ref "CCB48") (pin "2") (pinfunction "2_2") (pintype "passive"))
      (node (ref "IC2") (pin "41") (pinfunction "COMLN_41") (pintype "bidirectional"))
      (node (ref "RVC37") (pin "1") (pinfunction "1_1") (pintype "passive"))
      (node (ref "RVC38") (pin "2") (pinfunction "2_2") (pintype "passive"))
    )
    (net (code "88") (name "Net-(IC2-COMLP)") (class "Default")
      (node (ref "CCB51") (pin "2") (pinfunction "2_2") (pintype "passive"))
      (node (ref "IC2") (pin "40") (pinfunction "COMLP_40") (pintype "bidirectional"))
      (node (ref "RVC37") (pin "2") (pinfunction "2_2") (pintype "passive"))
      (node (ref "RVC39") (pin "2") (pinfunction "2_2") (pintype "passive"))
    )
    (net (code "89") (name "Net-(IC2-CVDD)") (class "Default")
      (node (ref "CCB40") (pin "2") (pinfunction "2_2") (pintype "passive"))
      (node (ref "IC2") (pin "45") (pinfunction "CVDD_45") (pintype "bidirectional"))
      (node (ref "IC2") (pin "52") (pinfunction "RX_52") (pintype "bidirectional"))
    )
    (net (code "90") (name "Net-(IC2-DVDD)") (class "Default")
      (node (ref "CCB41") (pin "2") (pinfunction "2_2") (pintype "passive"))
      (node (ref "IC2") (pin "49") (pinfunction "DVDD_49") (pintype "bidirectional"))
    )
    (net (code "91") (name "Net-(IC2-GPIO1)") (class "Default")
      (node (ref "IC2") (pin "61") (pinfunction "GPIO1_61") (pintype "bidirectional"))
      (node (ref "R16") (pin "2") (pinfunction "2_2") (pintype "passive"))
      (node (ref "X6") (pin "1") (pinfunction "S_1") (pintype "passive"))
    )
    (net (code "92") (name "Net-(IC2-GPIO2)") (class "Default")
      (node (ref "IC2") (pin "60") (pinfunction "GPIO2_60") (pintype "bidirectional"))
      (node (ref "R15") (pin "2") (pinfunction "2_2") (pintype "passive"))
      (node (ref "X6") (pin "2") (pinfunction "S_2") (pintype "passive"))
    )
    (net (code "93") (name "Net-(IC2-GPIO3)") (class "Default")
      (node (ref "IC2") (pin "59") (pinfunction "GPIO3_59") (pintype "bidirectional"))
      (node (ref "R14") (pin "2") (pinfunction "2_2") (pintype "passive"))
      (node (ref "X6") (pin "3") (pinfunction "S_3") (pintype "passive"))
    )
    (net (code "94") (name "Net-(IC2-GPIO4)") (class "Default")
      (node (ref "IC2") (pin "58") (pinfunction "GPIO4_58") (pintype "bidirectional"))
      (node (ref "R13") (pin "2") (pinfunction "2_2") (pintype "passive"))
      (node (ref "X6") (pin "4") (pinfunction "S_4") (pintype "passive"))
    )
    (net (code "95") (name "Net-(IC2-GPIO5)") (class "Default")
      (node (ref "IC2") (pin "57") (pinfunction "GPIO5_57") (pintype "bidirectional"))
      (node (ref "R12") (pin "2") (pinfunction "2_2") (pintype "passive"))
      (node (ref "X6") (pin "5") (pinfunction "S_5") (pintype "passive"))
    )
    (net (code "96") (name "Net-(IC2-GPIO6)") (class "Default")
      (node (ref "IC2") (pin "56") (pinfunction "GPIO6_56") (pintype "bidirectional"))
      (node (ref "R11") (pin "2") (pinfunction "2_2") (pintype "passive"))
      (node (ref "X6") (pin "6") (pinfunction "S_6") (pintype "passive"))
    )
    (net (code "97") (name "Net-(IC2-GPIO7)") (class "Default")
      (node (ref "IC2") (pin "55") (pinfunction "GPIO7_55") (pintype "bidirectional"))
      (node (ref "R10") (pin "2") (pinfunction "2_2") (pintype "passive"))
      (node (ref "X6") (pin "7") (pinfunction "S_7") (pintype "passive"))
    )
    (net (code "98") (name "Net-(IC2-GPIO8)") (class "Default")
      (node (ref "IC2") (pin "54") (pinfunction "GPIO8_54") (pintype "bidirectional"))
      (node (ref "R9") (pin "2") (pinfunction "2_2") (pintype "passive"))
      (node (ref "X6") (pin "8") (pinfunction "S_8") (pintype "passive"))
    )
    (net (code "99") (name "Net-(IC2-NEG5V)") (class "Default")
      (node (ref "CCB39") (pin "2") (pinfunction "2_2") (pintype "passive"))
      (node (ref "IC2") (pin "44") (pinfunction "NEG5V_44") (pintype "bidirectional"))
    )
    (net (code "100") (name "Net-(IC2-REFHP)") (class "Default")
      (node (ref "CCB37") (pin "2") (pinfunction "2_2") (pintype "passive"))
      (node (ref "IC2") (pin "37") (pinfunction "REFHP_37") (pintype "bidirectional"))
    )
    (net (code "101") (name "Net-(IC2-TSREF)") (class "Default")
      (node (ref "C2") (pin "2") (pinfunction "2_2") (pintype "passive"))
      (node (ref "IC2") (pin "51") (pinfunction "TSREF_51") (pintype "bidirectional"))
      (node (ref "R10") (pin "1") (pinfunction "1_1") (pintype "passive"))
      (node (ref "R11") (pin "1") (pinfunction "1_1") (pintype "passive"))
      (node (ref "R12") (pin "1") (pinfunction "1_1") (pintype "passive"))
      (node (ref "R13") (pin "1") (pinfunction "1_1") (pintype "passive"))
      (node (ref "R14") (pin "1") (pinfunction "1_1") (pintype "passive"))
      (node (ref "R15") (pin "1") (pinfunction "1_1") (pintype "passive"))
      (node (ref "R16") (pin "1") (pinfunction "1_1") (pintype "passive"))
      (node (ref "R9") (pin "1") (pinfunction "1_1") (pintype "passive"))
    )
    (net (code "102") (name "Net-(IC2-VC0)") (class "Default")
      (node (ref "IC2") (pin "35") (pinfunction "VC0_35") (pintype "bidirectional"))
      (node (ref "RVC30") (pin "2") (pinfunction "2_2") (pintype "passive"))
    )
    (net (code "103") (name "Net-(IC2-VC1)") (class "Default")
      (node (ref "IC2") (pin "33") (pinfunction "VC1_33") (pintype "bidirectional"))
      (node (ref "RVC20") (pin "2") (pinfunction "2_2") (pintype "passive"))
    )
    (net (code "104") (name "Net-(IC2-VC2)") (class "Default")
      (node (ref "IC2") (pin "31") (pinfunction "VC2_31") (pintype "bidirectional"))
      (node (ref "RVC21") (pin "2") (pinfunction "2_2") (pintype "passive"))
    )
    (net (code "105") (name "Net-(IC2-VC3)") (class "Default")
      (node (ref "IC2") (pin "29") (pinfunction "VC3_29") (pintype "bidirectional"))
      (node (ref "RVC22") (pin "2") (pinfunction "2_2") (pintype "passive"))
    )
    (net (code "106") (name "Net-(IC2-VC4)") (class "Default")
      (node (ref "IC2") (pin "27") (pinfunction "VC4_27") (pintype "bidirectional"))
      (node (ref "RVC23") (pin "2") (pinfunction "2_2") (pintype "passive"))
    )
    (net (code "107") (name "Net-(IC2-VC5)") (class "Default")
      (node (ref "IC2") (pin "25") (pinfunction "VC5_25") (pintype "bidirectional"))
      (node (ref "RVC24") (pin "2") (pinfunction "2_2") (pintype "passive"))
    )
    (net (code "108") (name "Net-(IC2-VC6)") (class "Default")
      (node (ref "IC2") (pin "23") (pinfunction "VC6_23") (pintype "bidirectional"))
      (node (ref "RVC25") (pin "2") (pinfunction "2_2") (pintype "passive"))
    )
    (net (code "109") (name "Net-(IC2-VC7)") (class "Default")
      (node (ref "IC2") (pin "21") (pinfunction "VC7_21") (pintype "bidirectional"))
      (node (ref "RVC26") (pin "2") (pinfunction "2_2") (pintype "passive"))
    )
    (net (code "110") (name "Net-(IC2-VC8)") (class "Default")
      (node (ref "IC2") (pin "19") (pinfunction "VC8_19") (pintype "bidirectional"))
      (node (ref "RVC27") (pin "2") (pinfunction "2_2") (pintype "passive"))
    )
    (net (code "111") (name "Net-(IC2-VC9)") (class "Default")
      (node (ref "IC2") (pin "17") (pinfunction "VC9_17") (pintype "bidirectional"))
      (node (ref "RVC28") (pin "2") (pinfunction "2_2") (pintype "passive"))
    )
    (net (code "112") (name "Net-(IC2-VC10)") (class "Default")
      (node (ref "IC2") (pin "15") (pinfunction "VC10_15") (pintype "bidirectional"))
      (node (ref "RVC29") (pin "2") (pinfunction "2_2") (pintype "passive"))
    )
    (net (code "113") (name "Net-(X1A-S)") (class "Default")
      (node (ref "CVC0") (pin "2") (pinfunction "2_2") (pintype "passive"))
      (node (ref "RVC0") (pin "1") (pinfunction "1_1") (pintype "passive"))
      (node (ref "X1") (pin "1") (pinfunction "S_1") (pintype "passive"))
    )
    (net (code "114") (name "Net-(X1B-S)") (class "Default")
      (node (ref "CVC8") (pin "1") (pinfunction "1_1") (pintype "passive"))
      (node (ref "CVC9") (pin "2") (pinfunction "2_2") (pintype "passive"))
      (node (ref "RVC9") (pin "1") (pinfunction "1_1") (pintype "passive"))
      (node (ref "X1") (pin "10") (pinfunction "S_10") (pintype "passive"))
    )
    (net (code "115") (name "Net-(X1C-S)") (class "Default")
      (node (ref "CVC9") (pin "1") (pinfunction "1_1") (pintype "passive"))
      (node (ref "RVC10") (pin "1") (pinfunction "1_1") (pintype "passive"))
      (node (ref "X1") (pin "11") (pinfunction "S_11") (pintype "passive"))
    )
    (net (code "116") (name "Net-(X1E-S)") (class "Default")
      (node (ref "CVC0") (pin "1") (pinfunction "1_1") (pintype "passive"))
      (node (ref "CVC1") (pin "2") (pinfunction "2_2") (pintype "passive"))
      (node (ref "RVC1") (pin "1") (pinfunction "1_1") (pintype "passive"))
      (node (ref "X1") (pin "2") (pinfunction "S_2") (pintype "passive"))
    )
    (net (code "117") (name "Net-(X1F-S)") (class "Default")
      (node (ref "CVC1") (pin "1") (pinfunction "1_1") (pintype "passive"))
      (node (ref "CVC2") (pin "2") (pinfunction "2_2") (pintype "passive"))
      (node (ref "RVC2") (pin "1") (pinfunction "1_1") (pintype "passive"))
      (node (ref "X1") (pin "3") (pinfunction "S_3") (pintype "passive"))
    )
    (net (code "118") (name "Net-(X1G-S)") (class "Default")
      (node (ref "CVC2") (pin "1") (pinfunction "1_1") (pintype "passive"))
      (node (ref "CVC3") (pin "2") (pinfunction "2_2") (pintype "passive"))
      (node (ref "RVC3") (pin "1") (pinfunction "1_1") (pintype "passive"))
      (node (ref "X1") (pin "4") (pinfunction "S_4") (pintype "passive"))
    )
    (net (code "119") (name "Net-(X1H-S)") (class "Default")
      (node (ref "CVC3") (pin "1") (pinfunction "1_1") (pintype "passive"))
      (node (ref "CVC4") (pin "2") (pinfunction "2_2") (pintype "passive"))
      (node (ref "RVC4") (pin "1") (pinfunction "1_1") (pintype "passive"))
      (node (ref "X1") (pin "5") (pinfunction "S_5") (pintype "passive"))
    )
    (net (code "120") (name "Net-(X1I-S)") (class "Default")
      (node (ref "CVC4") (pin "1") (pinfunction "1_1") (pintype "passive"))
      (node (ref "CVC5") (pin "2") (pinfunction "2_2") (pintype "passive"))
      (node (ref "RVC5") (pin "1") (pinfunction "1_1") (pintype "passive"))
      (node (ref "X1") (pin "6") (pinfunction "S_6") (pintype "passive"))
    )
    (net (code "121") (name "Net-(X1J-S)") (class "Default")
      (node (ref "CVC5") (pin "1") (pinfunction "1_1") (pintype "passive"))
      (node (ref "CVC6") (pin "2") (pinfunction "2_2") (pintype "passive"))
      (node (ref "RVC6") (pin "1") (pinfunction "1_1") (pintype "passive"))
      (node (ref "X1") (pin "7") (pinfunction "S_7") (pintype "passive"))
    )
    (net (code "122") (name "Net-(X1K-S)") (class "Default")
      (node (ref "CVC6") (pin "1") (pinfunction "1_1") (pintype "passive"))
      (node (ref "CVC7") (pin "2") (pinfunction "2_2") (pintype "passive"))
      (node (ref "RVC7") (pin "1") (pinfunction "1_1") (pintype "passive"))
      (node (ref "X1") (pin "8") (pinfunction "S_8") (pintype "passive"))
    )
    (net (code "123") (name "Net-(X1L-S)") (class "Default")
      (node (ref "CVC7") (pin "1") (pinfunction "1_1") (pintype "passive"))
      (node (ref "CVC8") (pin "2") (pinfunction "2_2") (pintype "passive"))
      (node (ref "RVC8") (pin "1") (pinfunction "1_1") (pintype "passive"))
      (node (ref "X1") (pin "9") (pinfunction "S_9") (pintype "passive"))
    )
    (net (code "124") (name "Net-(X2B-S)") (class "Default")
      (node (ref "RCB9") (pin "1") (pinfunction "1_1") (pintype "passive"))
      (node (ref "X2") (pin "10") (pinfunction "S_10") (pintype "passive"))
    )
    (net (code "125") (name "Net-(X2E-S)") (class "Default")
      (node (ref "RCB1") (pin "1") (pinfunction "1_1") (pintype "passive"))
      (node (ref "X2") (pin "2") (pinfunction "S_2") (pintype "passive"))
    )
    (net (code "126") (name "Net-(X2F-S)") (class "Default")
      (node (ref "RCB2") (pin "1") (pinfunction "1_1") (pintype "passive"))
      (node (ref "X2") (pin "3") (pinfunction "S_3") (pintype "passive"))
    )
    (net (code "127") (name "Net-(X2G-S)") (class "Default")
      (node (ref "RCB3") (pin "1") (pinfunction "1_1") (pintype "passive"))
      (node (ref "X2") (pin "4") (pinfunction "S_4") (pintype "passive"))
    )
    (net (code "128") (name "Net-(X2H-S)") (class "Default")
      (node (ref "RCB4") (pin "1") (pinfunction "1_1") (pintype "passive"))
      (node (ref "X2") (pin "5") (pinfunction "S_5") (pintype "passive"))
    )
    (net (code "129") (name "Net-(X2I-S)") (class "Default")
      (node (ref "RCB5") (pin "1") (pinfunction "1_1") (pintype "passive"))
      (node (ref "X2") (pin "6") (pinfunction "S_6") (pintype "passive"))
    )
    (net (code "130") (name "Net-(X2J-S)") (class "Default")
      (node (ref "RCB6") (pin "1") (pinfunction "1_1") (pintype "passive"))
      (node (ref "X2") (pin "7") (pinfunction "S_7") (pintype "passive"))
    )
    (net (code "131") (name "Net-(X2K-S)") (class "Default")
      (node (ref "RCB7") (pin "1") (pinfunction "1_1") (pintype "passive"))
      (node (ref "X2") (pin "8") (pinfunction "S_8") (pintype "passive"))
    )
    (net (code "132") (name "Net-(X2L-S)") (class "Default")
      (node (ref "RCB8") (pin "1") (pinfunction "1_1") (pintype "passive"))
      (node (ref "X2") (pin "9") (pinfunction "S_9") (pintype "passive"))
    )
    (net (code "133") (name "Net-(X4A-S)") (class "Default")
      (node (ref "CVC19") (pin "2") (pinfunction "2_2") (pintype "passive"))
      (node (ref "RVC30") (pin "1") (pinfunction "1_1") (pintype "passive"))
      (node (ref "X4") (pin "1") (pinfunction "S_1") (pintype "passive"))
    )
    (net (code "134") (name "Net-(X4B-S)") (class "Default")
      (node (ref "CVC17") (pin "1") (pinfunction "1_1") (pintype "passive"))
      (node (ref "CVC18") (pin "2") (pinfunction "2_2") (pintype "passive"))
      (node (ref "RVC28") (pin "1") (pinfunction "1_1") (pintype "passive"))
      (node (ref "X4") (pin "10") (pinfunction "S_10") (pintype "passive"))
    )
    (net (code "135") (name "Net-(X4C-S)") (class "Default")
      (node (ref "CVC18") (pin "1") (pinfunction "1_1") (pintype "passive"))
      (node (ref "RVC29") (pin "1") (pinfunction "1_1") (pintype "passive"))
      (node (ref "X4") (pin "11") (pinfunction "S_11") (pintype "passive"))
    )
    (net (code "136") (name "Net-(X4E-S)") (class "Default")
      (node (ref "CVC10") (pin "2") (pinfunction "2_2") (pintype "passive"))
      (node (ref "CVC19") (pin "1") (pinfunction "1_1") (pintype "passive"))
      (node (ref "RVC20") (pin "1") (pinfunction "1_1") (pintype "passive"))
      (node (ref "X4") (pin "2") (pinfunction "S_2") (pintype "passive"))
    )
    (net (code "137") (name "Net-(X4F-S)") (class "Default")
      (node (ref "CVC10") (pin "1") (pinfunction "1_1") (pintype "passive"))
      (node (ref "CVC11") (pin "2") (pinfunction "2_2") (pintype "passive"))
      (node (ref "RVC21") (pin "1") (pinfunction "1_1") (pintype "passive"))
      (node (ref "X4") (pin "3") (pinfunction "S_3") (pintype "passive"))
    )
    (net (code "138") (name "Net-(X4G-S)") (class "Default")
      (node (ref "CVC11") (pin "1") (pinfunction "1_1") (pintype "passive"))
      (node (ref "CVC12") (pin "2") (pinfunction "2_2") (pintype "passive"))
      (node (ref "RVC22") (pin "1") (pinfunction "1_1") (pintype "passive"))
      (node (ref "X4") (pin "4") (pinfunction "S_4") (pintype "passive"))
    )
    (net (code "139") (name "Net-(X4H-S)") (class "Default")
      (node (ref "CVC12") (pin "1") (pinfunction "1_1") (pintype "passive"))
      (node (ref "CVC13") (pin "2") (pinfunction "2_2") (pintype "passive"))
      (node (ref "RVC23") (pin "1") (pinfunction "1_1") (pintype "passive"))
      (node (ref "X4") (pin "5") (pinfunction "S_5") (pintype "passive"))
    )
    (net (code "140") (name "Net-(X4I-S)") (class "Default")
      (node (ref "CVC13") (pin "1") (pinfunction "1_1") (pintype "passive"))
      (node (ref "CVC14") (pin "2") (pinfunction "2_2") (pintype "passive"))
      (node (ref "RVC24") (pin "1") (pinfunction "1_1") (pintype "passive"))
      (node (ref "X4") (pin "6") (pinfunction "S_6") (pintype "passive"))
    )
    (net (code "141") (name "Net-(X4J-S)") (class "Default")
      (node (ref "CVC14") (pin "1") (pinfunction "1_1") (pintype "passive"))
      (node (ref "CVC15") (pin "2") (pinfunction "2_2") (pintype "passive"))
      (node (ref "RVC25") (pin "1") (pinfunction "1_1") (pintype "passive"))
      (node (ref "X4") (pin "7") (pinfunction "S_7") (pintype "passive"))
    )
    (net (code "142") (name "Net-(X4K-S)") (class "Default")
      (node (ref "CVC15") (pin "1") (pinfunction "1_1") (pintype "passive"))
      (node (ref "CVC16") (pin "2") (pinfunction "2_2") (pintype "passive"))
      (node (ref "RVC26") (pin "1") (pinfunction "1_1") (pintype "passive"))
      (node (ref "X4") (pin "8") (pinfunction "S_8") (pintype "passive"))
    )
    (net (code "143") (name "Net-(X4L-S)") (class "Default")
      (node (ref "CVC16") (pin "1") (pinfunction "1_1") (pintype "passive"))
      (node (ref "CVC17") (pin "2") (pinfunction "2_2") (pintype "passive"))
      (node (ref "RVC27") (pin "1") (pinfunction "1_1") (pintype "passive"))
      (node (ref "X4") (pin "9") (pinfunction "S_9") (pintype "passive"))
    )
    (net (code "144") (name "Net-(X5B-S)") (class "Default")
      (node (ref "RCB20") (pin "1") (pinfunction "1_1") (pintype "passive"))
      (node (ref "X5") (pin "10") (pinfunction "S_10") (pintype "passive"))
    )
    (net (code "145") (name "Net-(X5E-S)") (class "Default")
      (node (ref "RCB12") (pin "1") (pinfunction "1_1") (pintype "passive"))
      (node (ref "X5") (pin "2") (pinfunction "S_2") (pintype "passive"))
    )
    (net (code "146") (name "Net-(X5F-S)") (class "Default")
      (node (ref "RCB13") (pin "1") (pinfunction "1_1") (pintype "passive"))
      (node (ref "X5") (pin "3") (pinfunction "S_3") (pintype "passive"))
    )
    (net (code "147") (name "Net-(X5G-S)") (class "Default")
      (node (ref "RCB14") (pin "1") (pinfunction "1_1") (pintype "passive"))
      (node (ref "X5") (pin "4") (pinfunction "S_4") (pintype "passive"))
    )
    (net (code "148") (name "Net-(X5H-S)") (class "Default")
      (node (ref "RCB15") (pin "1") (pinfunction "1_1") (pintype "passive"))
      (node (ref "X5") (pin "5") (pinfunction "S_5") (pintype "passive"))
    )
    (net (code "149") (name "Net-(X5I-S)") (class "Default")
      (node (ref "RCB16") (pin "1") (pinfunction "1_1") (pintype "passive"))
      (node (ref "X5") (pin "6") (pinfunction "S_6") (pintype "passive"))
    )
    (net (code "150") (name "Net-(X5J-S)") (class "Default")
      (node (ref "RCB17") (pin "1") (pinfunction "1_1") (pintype "passive"))
      (node (ref "X5") (pin "7") (pinfunction "S_7") (pintype "passive"))
    )
    (net (code "151") (name "Net-(X5K-S)") (class "Default")
      (node (ref "RCB18") (pin "1") (pinfunction "1_1") (pintype "passive"))
      (node (ref "X5") (pin "8") (pinfunction "S_8") (pintype "passive"))
    )
    (net (code "152") (name "Net-(X5L-S)") (class "Default")
      (node (ref "RCB19") (pin "1") (pinfunction "1_1") (pintype "passive"))
      (node (ref "X5") (pin "9") (pinfunction "S_9") (pintype "passive"))
    )
    (net (code "153") (name "unconnected-(CCB24-Pad1)") (class "Default")
      (node (ref "CCB24") (pin "1") (pinfunction "1_1") (pintype "passive"))
    )
    (net (code "154") (name "unconnected-(CCB25-Pad1)") (class "Default")
      (node (ref "CCB25") (pin "1") (pinfunction "1_1") (pintype "passive"))
    )
    (net (code "155") (name "unconnected-(IC1-BBN(SRN)-Pad63)") (class "Default")
      (node (ref "IC1") (pin "63") (pinfunction "BBN(SRN)_63") (pintype "bidirectional"))
    )
    (net (code "156") (name "unconnected-(IC1-BBP(SRP)-Pad64)") (class "Default")
      (node (ref "IC1") (pin "64") (pinfunction "BBP(SRP)_64") (pintype "bidirectional"))
    )
    (net (code "157") (name "unconnected-(IC1-NFAULT-Pad62)") (class "Default")
      (node (ref "IC1") (pin "62") (pinfunction "NFAULT_62") (pintype "bidirectional"))
    )
    (net (code "158") (name "unconnected-(IC1-TX-Pad53)") (class "Default")
      (node (ref "IC1") (pin "53") (pinfunction "TX_53") (pintype "bidirectional"))
    )
    (net (code "159") (name "unconnected-(IC2-BBN(SRN)-Pad63)") (class "Default")
      (node (ref "IC2") (pin "63") (pinfunction "BBN(SRN)_63") (pintype "bidirectional"))
    )
    (net (code "160") (name "unconnected-(IC2-BBP(SRP)-Pad64)") (class "Default")
      (node (ref "IC2") (pin "64") (pinfunction "BBP(SRP)_64") (pintype "bidirectional"))
    )
    (net (code "161") (name "unconnected-(IC2-NFAULT-Pad62)") (class "Default")
      (node (ref "IC2") (pin "62") (pinfunction "NFAULT_62") (pintype "bidirectional"))
    )
    (net (code "162") (name "unconnected-(IC2-TX-Pad53)") (class "Default")
      (node (ref "IC2") (pin "53") (pinfunction "TX_53") (pintype "bidirectional"))
    )
    (net (code "163") (name "unconnected-(RVC13-Pad1)") (class "Default")
      (node (ref "RVC13") (pin "1") (pinfunction "1_1") (pintype "passive"))
    )
    (net (code "164") (name "unconnected-(RVC14-Pad1)") (class "Default")
      (node (ref "RVC14") (pin "1") (pinfunction "1_1") (pintype "passive"))
    )
    (net (code "165") (name "unconnected-(X1D-S-Pad12)") (class "Default")
      (node (ref "X1") (pin "12") (pinfunction "S_12") (pintype "passive"))
    )
    (net (code "166") (name "unconnected-(X2D-S-Pad12)") (class "Default")
      (node (ref "X2") (pin "12") (pinfunction "S_12") (pintype "passive"))
    )
    (net (code "167") (name "unconnected-(X4D-S-Pad12)") (class "Default")
      (node (ref "X4") (pin "12") (pinfunction "S_12") (pintype "passive"))
    )
    (net (code "168") (name "unconnected-(X5D-S-Pad12)") (class "Default")
      (node (ref "X5") (pin "12") (pinfunction "S_12") (pintype "passive"))
    )
  )
)
